# MeinMarlin.net
KiCad netlist of a schematic drawn in EasyEDA
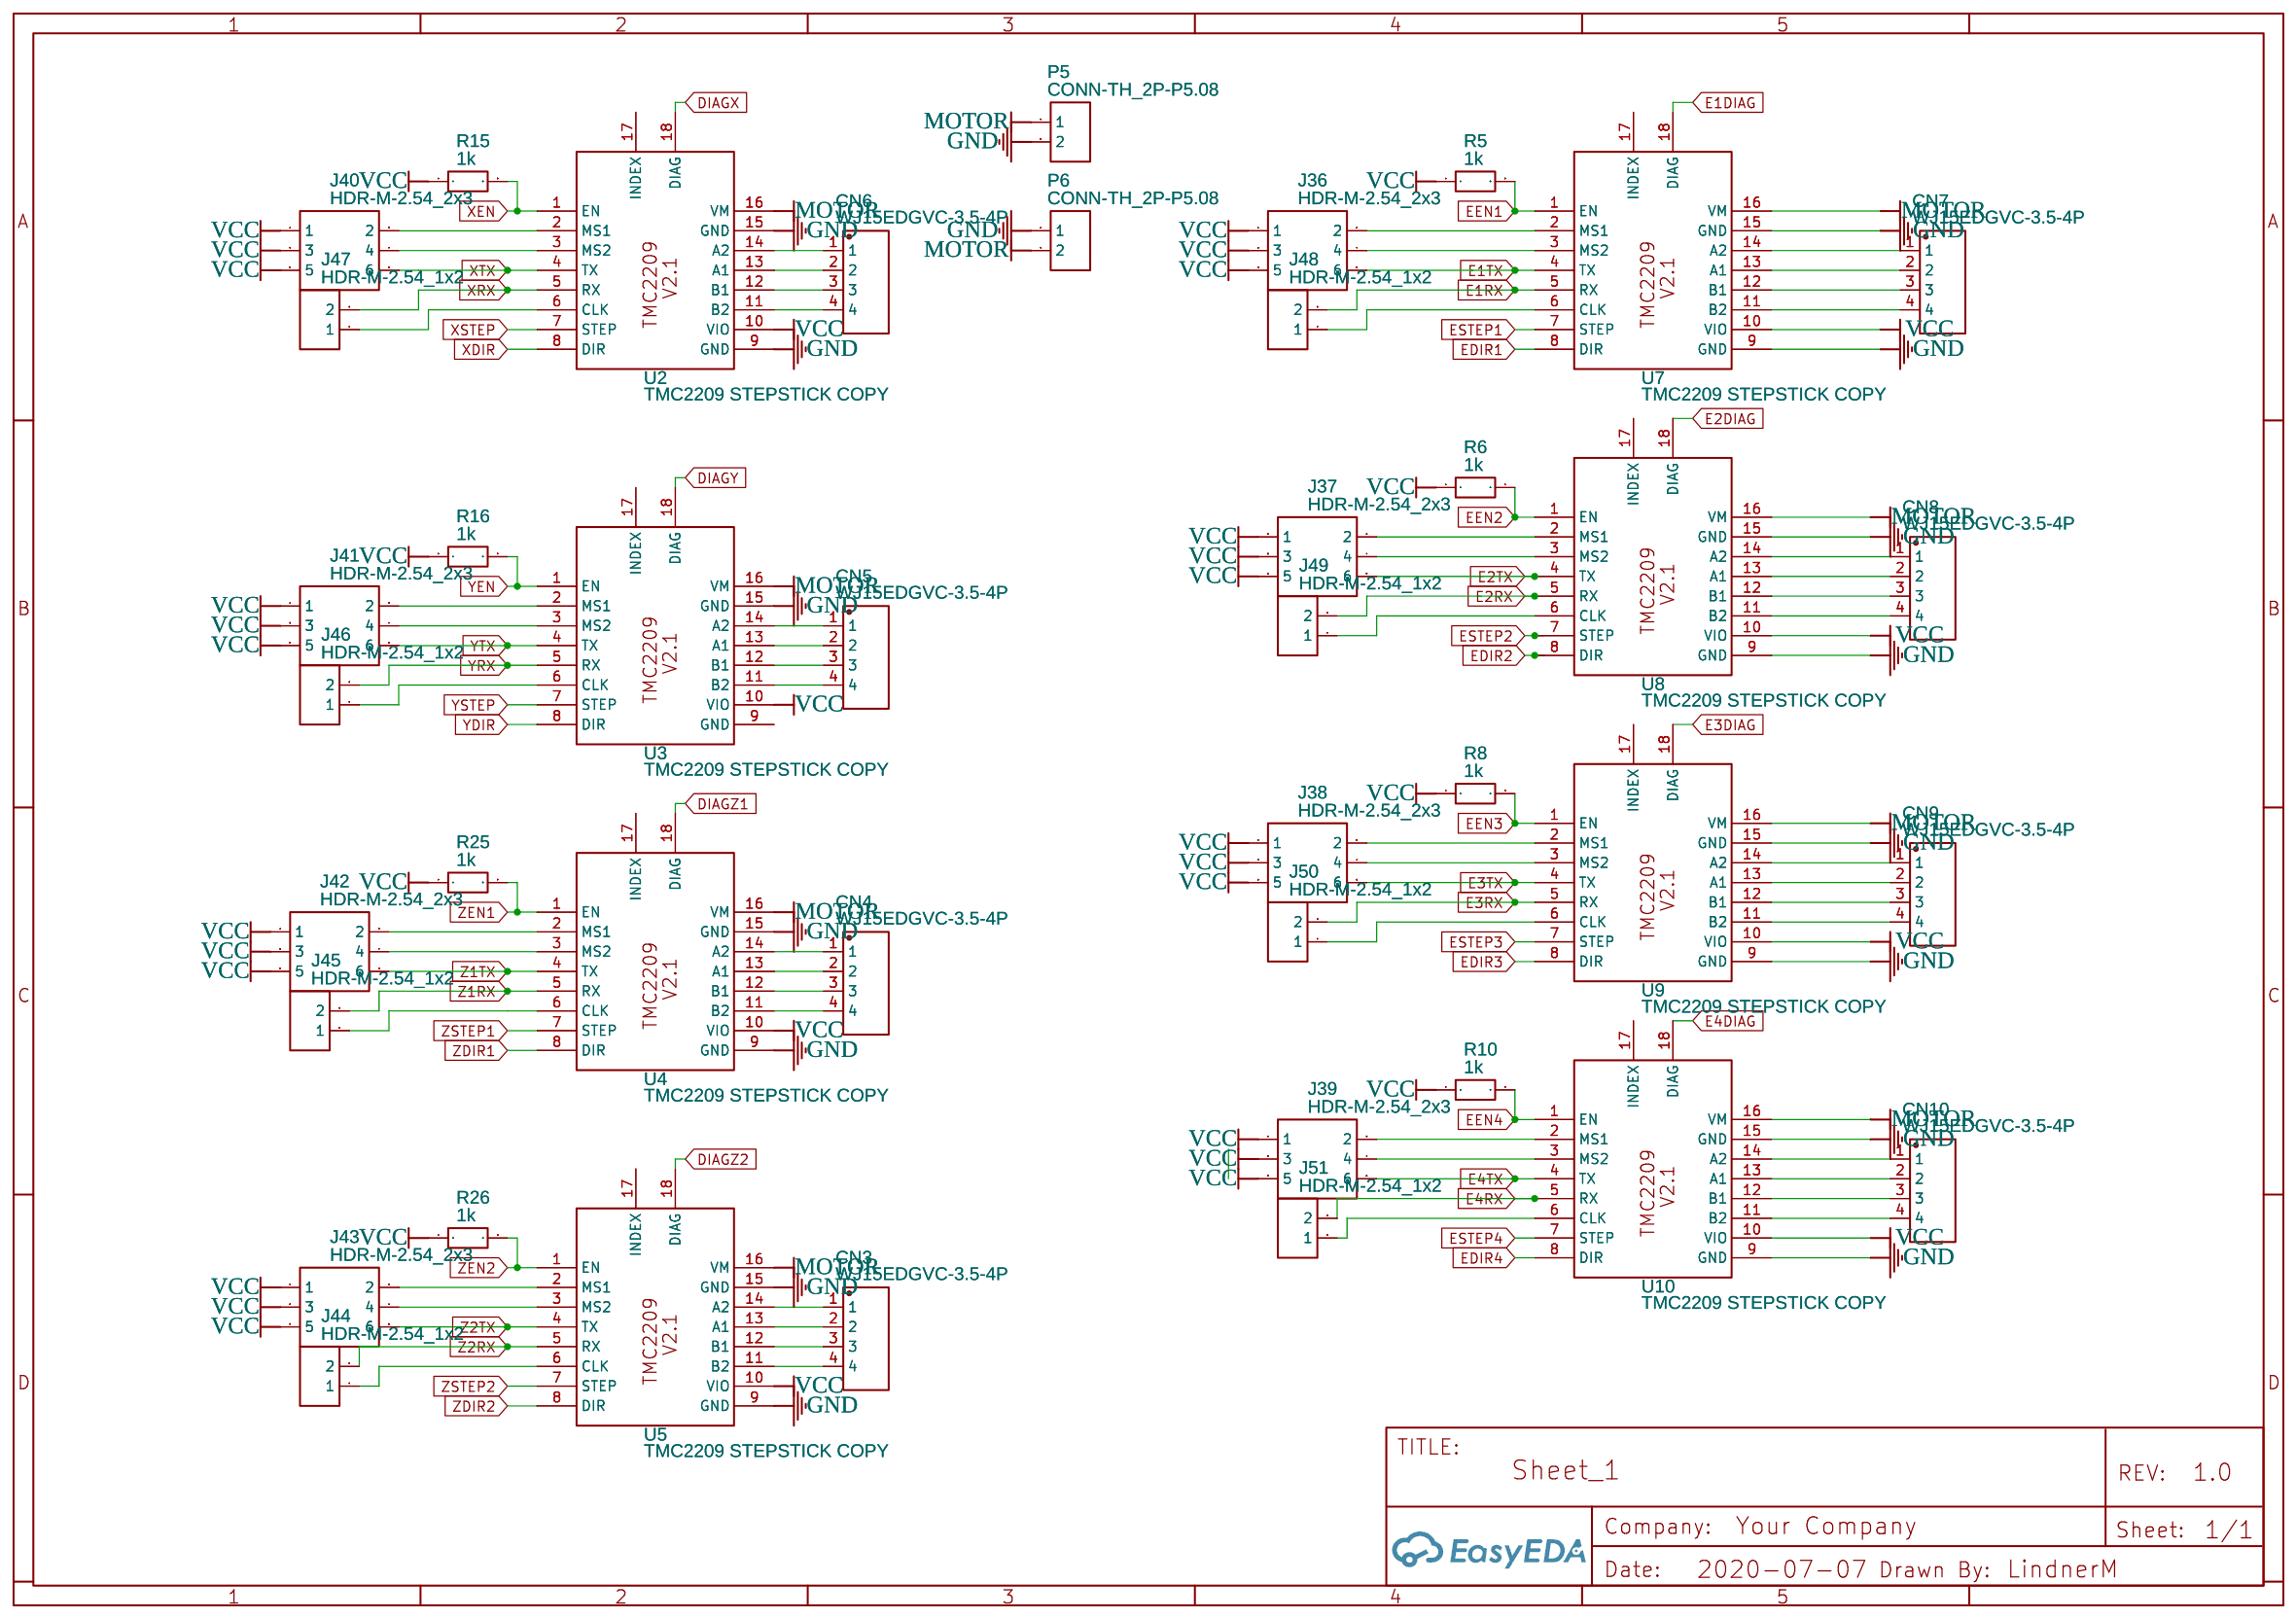
[diagram p0: STEPPER]
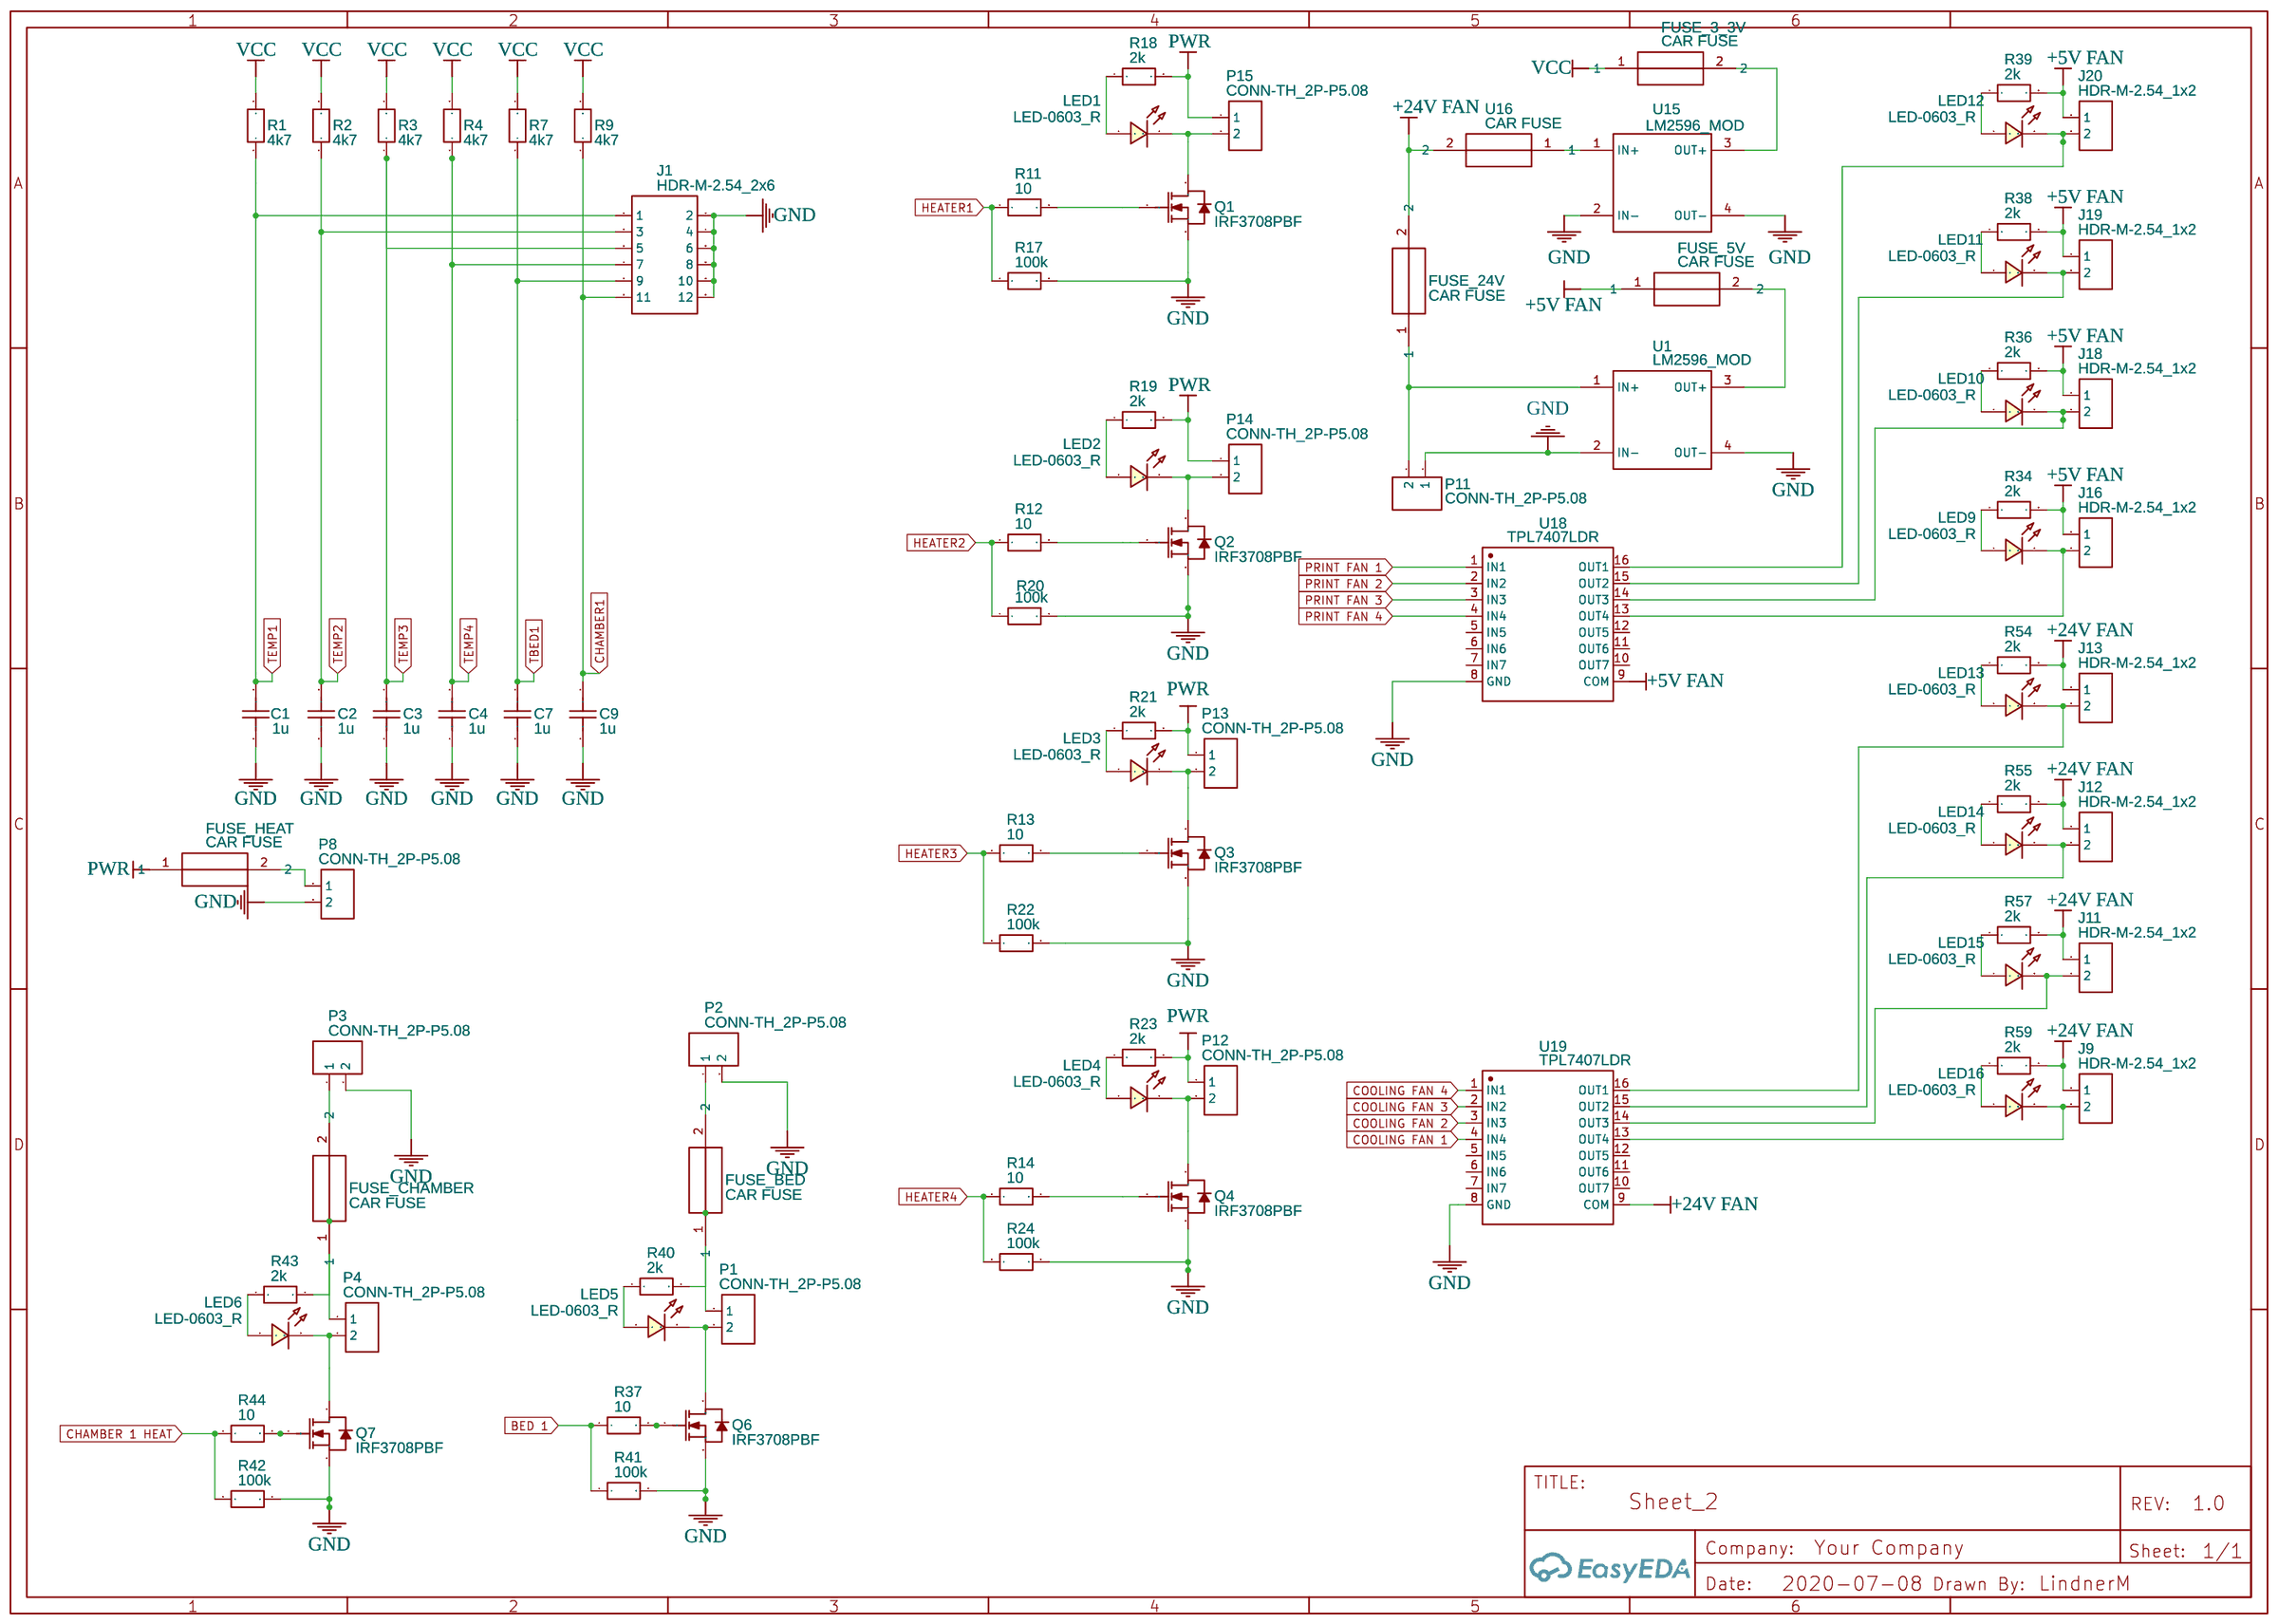
[diagram p1: FAN_HEAT_TEMP]
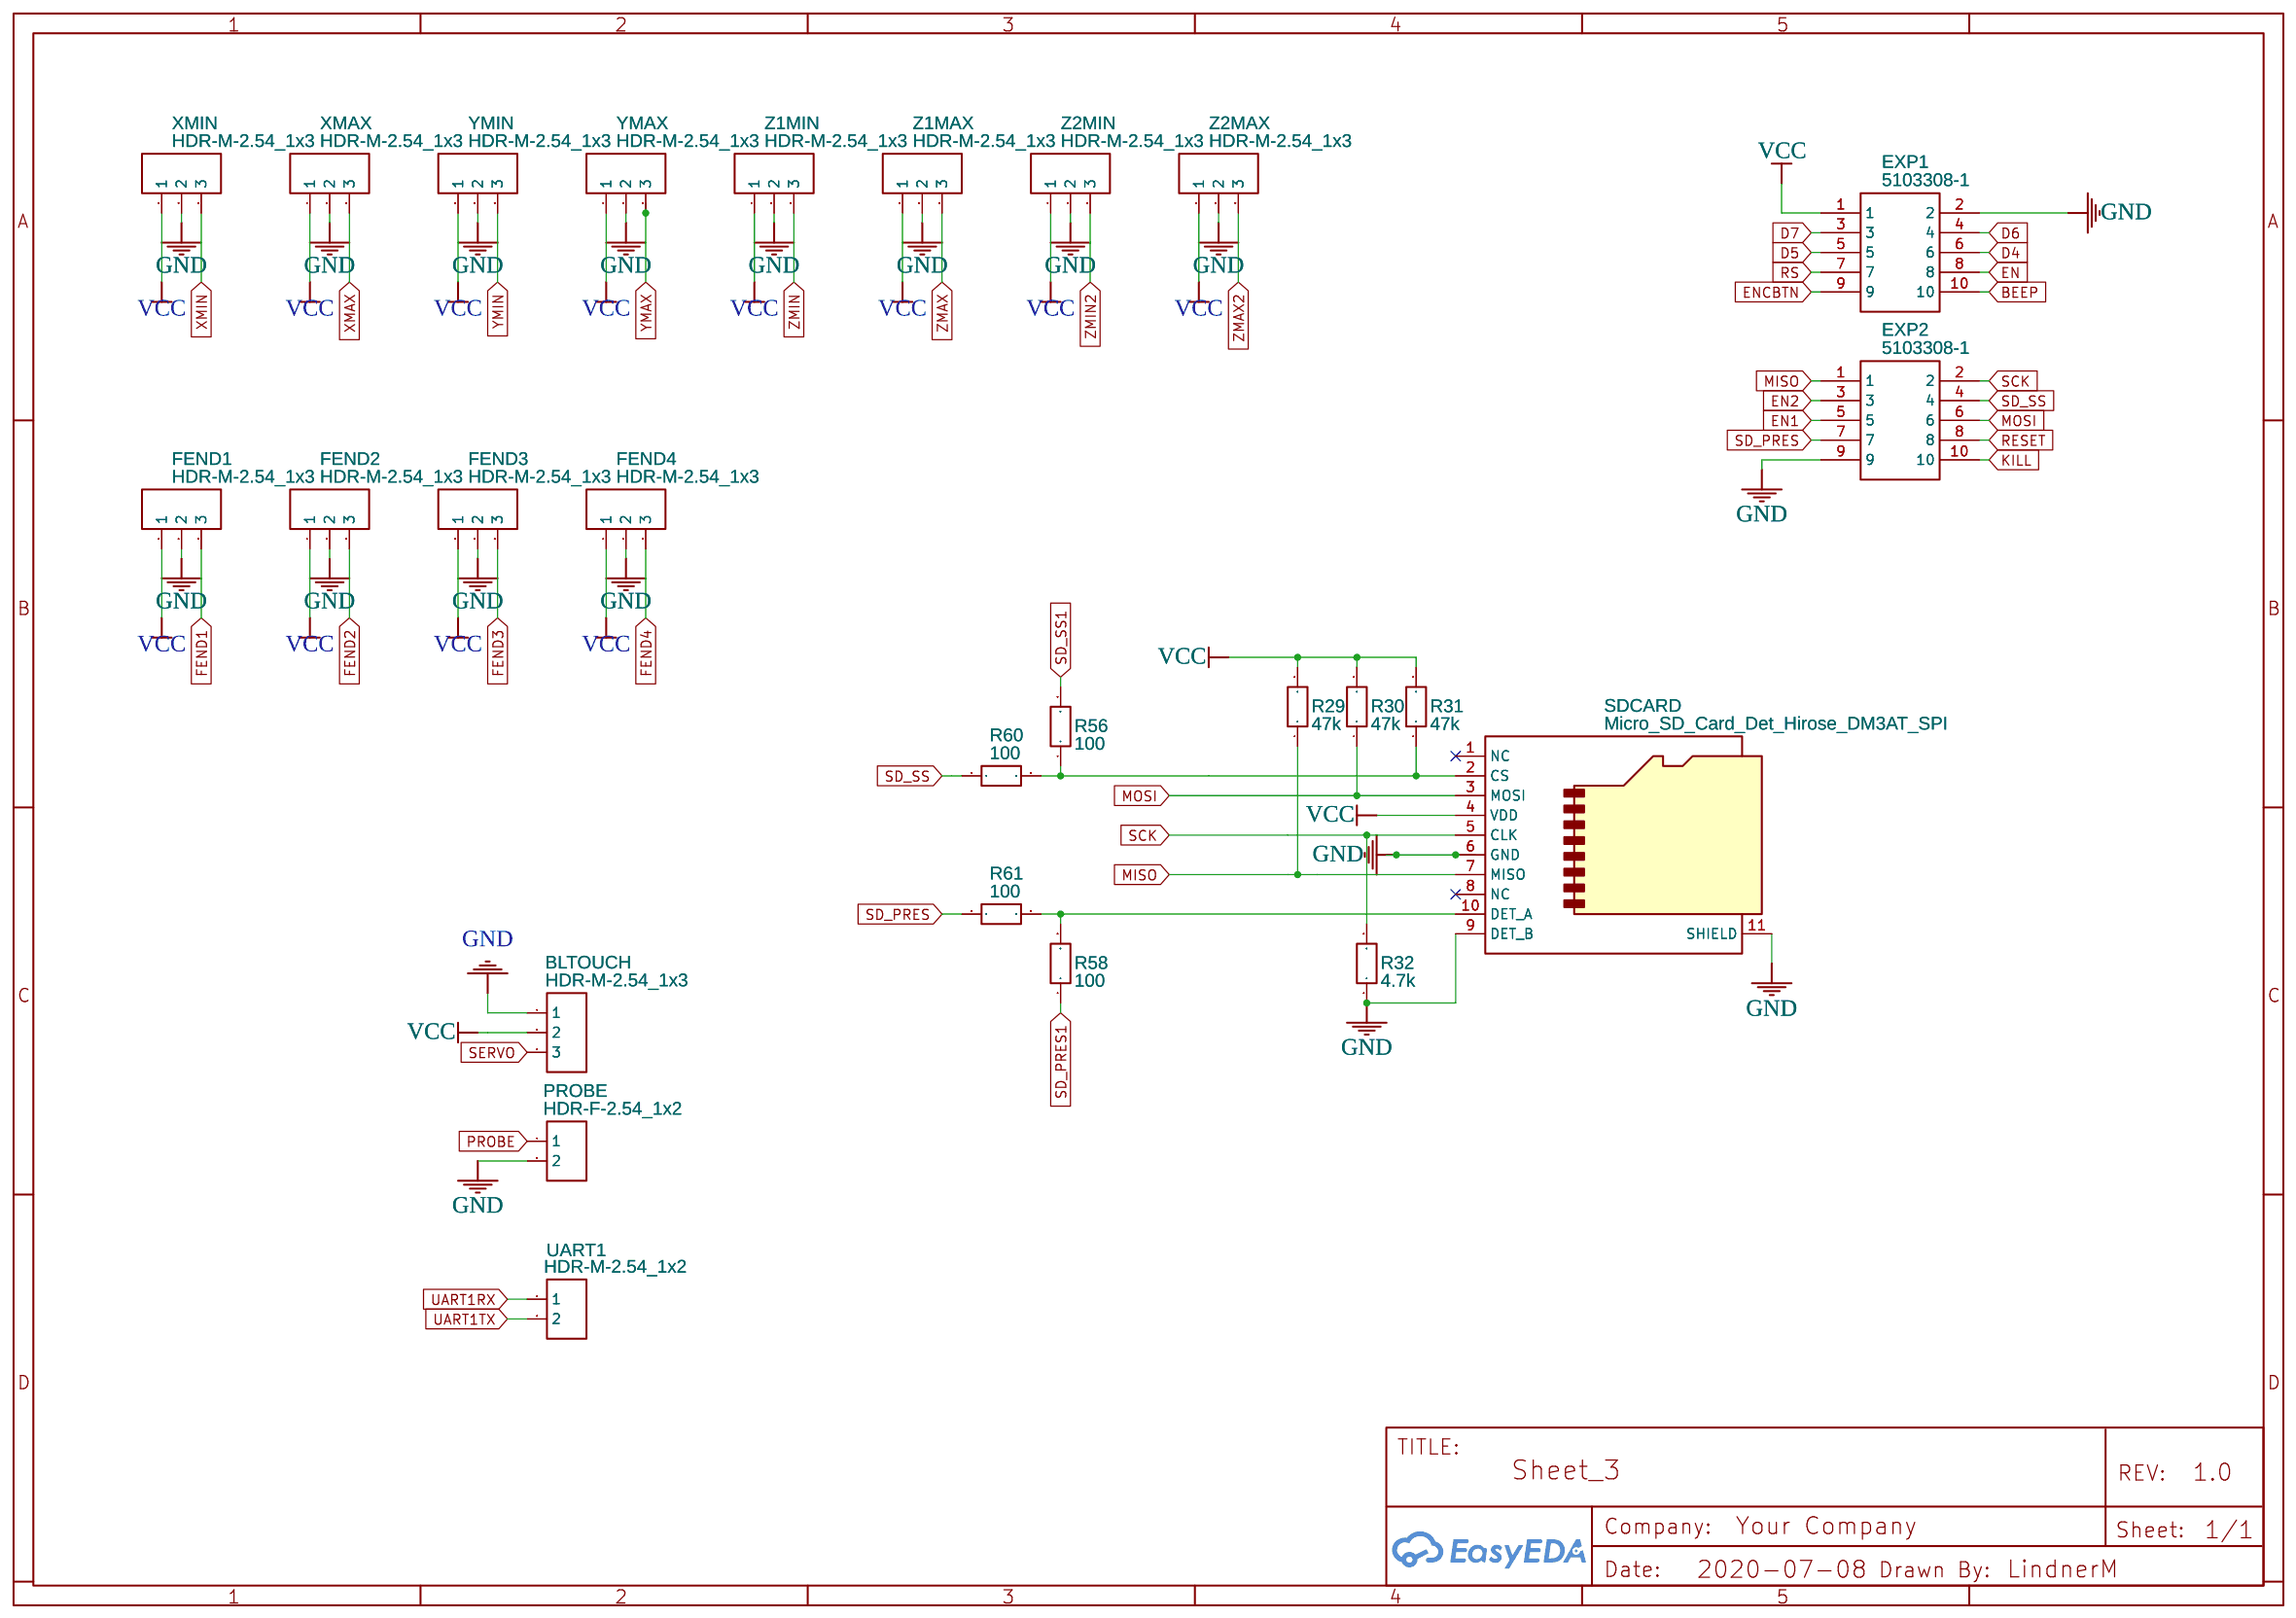
[diagram p2: SENSOR]
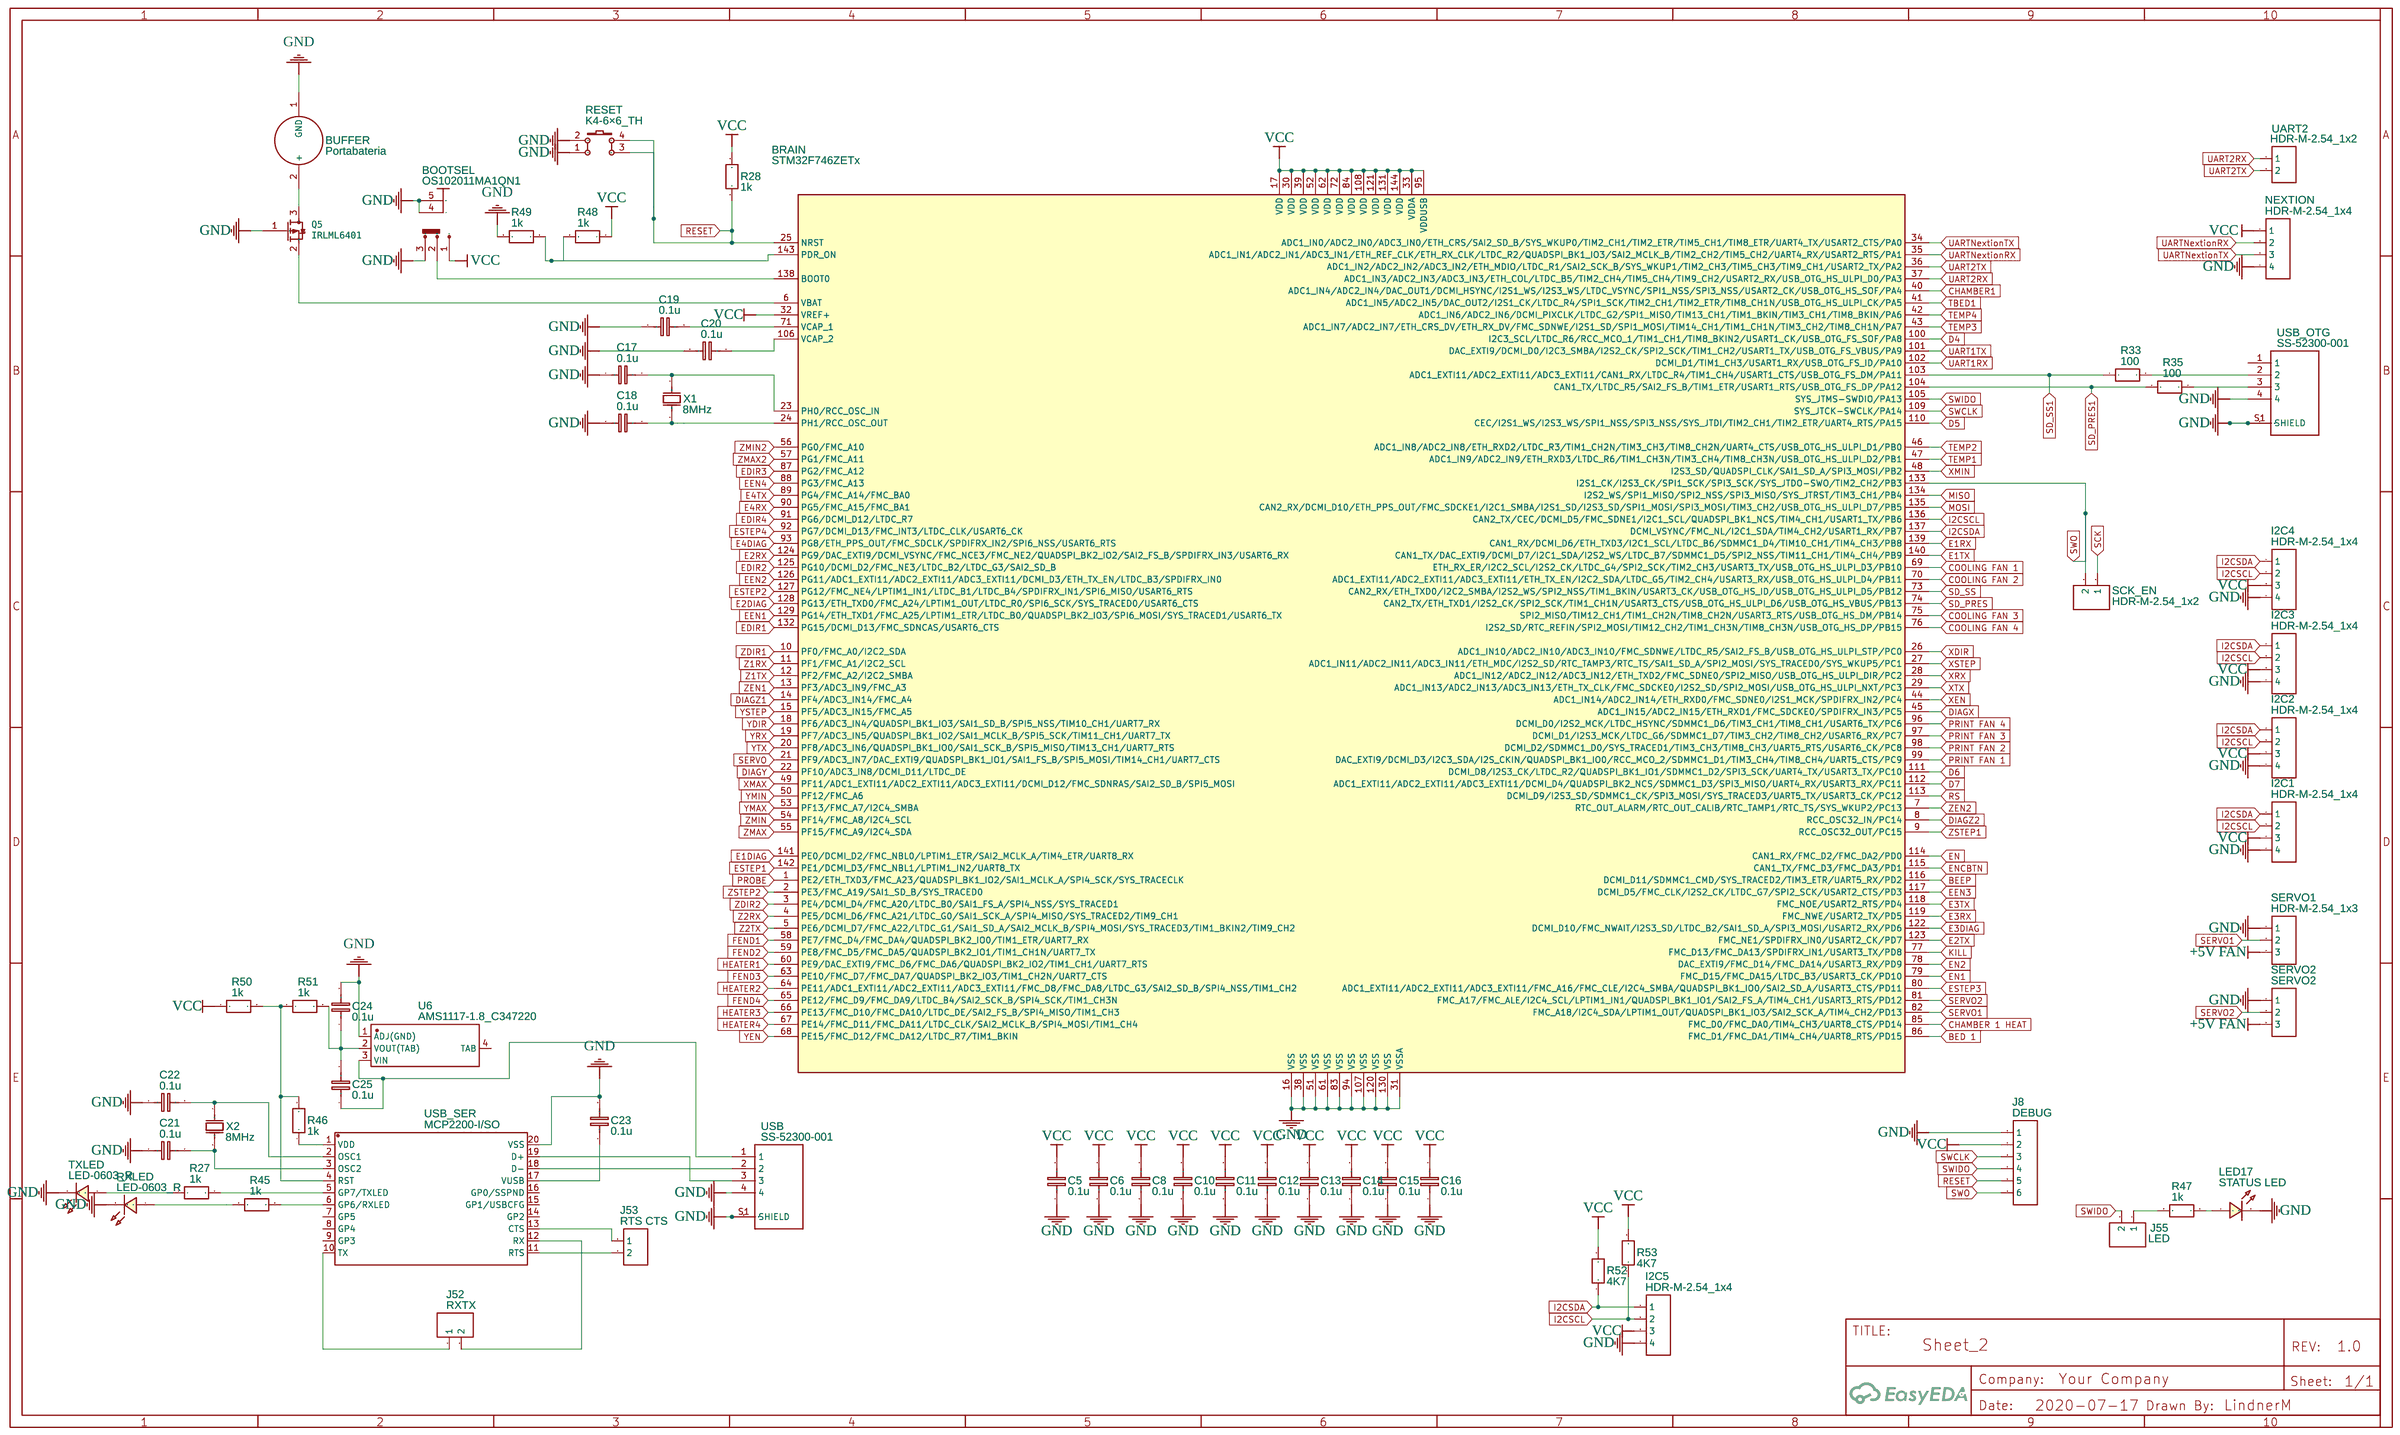
[diagram p3: MCU]

(export (version "E")
  (design (tool "Eeschema 10.0.6"))
  (components
    (comp (ref "CN3")
      (value "WJ15EDGVC-3.5-4P")
      (fields
        (field (name "BOM_Manufacturer Part") "WJ15EDGVC-3.5-4Pneedle")
        (field (name "BOM_Supplier Part") "C44917")
      )
      (libsource (lib "") (part "WJ15EDGVC-3.5-4P"))
    )
    (comp (ref "CN4")
      (value "WJ15EDGVC-3.5-4P")
      (fields
        (field (name "BOM_Manufacturer Part") "WJ15EDGVC-3.5-4Pneedle")
        (field (name "BOM_Supplier Part") "C44917")
      )
      (libsource (lib "") (part "WJ15EDGVC-3.5-4P"))
    )
    (comp (ref "CN5")
      (value "WJ15EDGVC-3.5-4P")
      (fields
        (field (name "BOM_Manufacturer Part") "WJ15EDGVC-3.5-4Pneedle")
        (field (name "BOM_Supplier Part") "C44917")
      )
      (libsource (lib "") (part "WJ15EDGVC-3.5-4P"))
    )
    (comp (ref "CN6")
      (value "WJ15EDGVC-3.5-4P")
      (fields
        (field (name "BOM_Manufacturer Part") "WJ15EDGVC-3.5-4Pneedle")
        (field (name "BOM_Supplier Part") "C44917")
      )
      (libsource (lib "") (part "WJ15EDGVC-3.5-4P"))
    )
    (comp (ref "CN7")
      (value "WJ15EDGVC-3.5-4P")
      (fields
        (field (name "BOM_Manufacturer Part") "WJ15EDGVC-3.5-4Pneedle")
        (field (name "BOM_Supplier Part") "C44917")
      )
      (libsource (lib "") (part "WJ15EDGVC-3.5-4P"))
    )
    (comp (ref "CN8")
      (value "WJ15EDGVC-3.5-4P")
      (fields
        (field (name "BOM_Manufacturer Part") "WJ15EDGVC-3.5-4Pneedle")
        (field (name "BOM_Supplier Part") "C44917")
      )
      (libsource (lib "") (part "WJ15EDGVC-3.5-4P"))
    )
    (comp (ref "CN9")
      (value "WJ15EDGVC-3.5-4P")
      (fields
        (field (name "BOM_Manufacturer Part") "WJ15EDGVC-3.5-4Pneedle")
        (field (name "BOM_Supplier Part") "C44917")
      )
      (libsource (lib "") (part "WJ15EDGVC-3.5-4P"))
    )
    (comp (ref "CN10")
      (value "WJ15EDGVC-3.5-4P")
      (fields
        (field (name "BOM_Manufacturer Part") "WJ15EDGVC-3.5-4Pneedle")
        (field (name "BOM_Supplier Part") "C44917")
      )
      (libsource (lib "") (part "WJ15EDGVC-3.5-4P"))
    )
    (comp (ref "J36")
      (value "HDR-M-2.54_2x3")
      (fields (field (name "BOM_Supplier Part") "C65114"))
      (libsource (lib "") (part "HDR-M-2.54_2x3"))
    )
    (comp (ref "J37")
      (value "HDR-M-2.54_2x3")
      (fields (field (name "BOM_Supplier Part") "C65114"))
      (libsource (lib "") (part "HDR-M-2.54_2x3"))
    )
    (comp (ref "J38")
      (value "HDR-M-2.54_2x3")
      (fields (field (name "BOM_Supplier Part") "C65114"))
      (libsource (lib "") (part "HDR-M-2.54_2x3"))
    )
    (comp (ref "J39")
      (value "HDR-M-2.54_2x3")
      (fields (field (name "BOM_Supplier Part") "C65114"))
      (libsource (lib "") (part "HDR-M-2.54_2x3"))
    )
    (comp (ref "J40")
      (value "HDR-M-2.54_2x3")
      (fields (field (name "BOM_Supplier Part") "C65114"))
      (libsource (lib "") (part "HDR-M-2.54_2x3"))
    )
    (comp (ref "J41")
      (value "HDR-M-2.54_2x3")
      (fields (field (name "BOM_Supplier Part") "C65114"))
      (libsource (lib "") (part "HDR-M-2.54_2x3"))
    )
    (comp (ref "J42")
      (value "HDR-M-2.54_2x3")
      (fields (field (name "BOM_Supplier Part") "C65114"))
      (libsource (lib "") (part "HDR-M-2.54_2x3"))
    )
    (comp (ref "J43")
      (value "HDR-M-2.54_2x3")
      (fields (field (name "BOM_Supplier Part") "C65114"))
      (libsource (lib "") (part "HDR-M-2.54_2x3"))
    )
    (comp (ref "J44")
      (value "HDR-M-2.54_1x2")
      (fields (field (name "BOM_Supplier Part") "C124375"))
      (libsource (lib "") (part "HDR-M-2.54_1x2"))
    )
    (comp (ref "J45")
      (value "HDR-M-2.54_1x2")
      (fields (field (name "BOM_Supplier Part") "C124375"))
      (libsource (lib "") (part "HDR-M-2.54_1x2"))
    )
    (comp (ref "J46")
      (value "HDR-M-2.54_1x2")
      (fields (field (name "BOM_Supplier Part") "C124375"))
      (libsource (lib "") (part "HDR-M-2.54_1x2"))
    )
    (comp (ref "J47")
      (value "HDR-M-2.54_1x2")
      (fields (field (name "BOM_Supplier Part") "C124375"))
      (libsource (lib "") (part "HDR-M-2.54_1x2"))
    )
    (comp (ref "J48")
      (value "HDR-M-2.54_1x2")
      (fields (field (name "BOM_Supplier Part") "C124375"))
      (libsource (lib "") (part "HDR-M-2.54_1x2"))
    )
    (comp (ref "J49")
      (value "HDR-M-2.54_1x2")
      (fields (field (name "BOM_Supplier Part") "C124375"))
      (libsource (lib "") (part "HDR-M-2.54_1x2"))
    )
    (comp (ref "J50")
      (value "HDR-M-2.54_1x2")
      (fields (field (name "BOM_Supplier Part") "C124375"))
      (libsource (lib "") (part "HDR-M-2.54_1x2"))
    )
    (comp (ref "J51")
      (value "HDR-M-2.54_1x2")
      (fields (field (name "BOM_Supplier Part") "C124375"))
      (libsource (lib "") (part "HDR-M-2.54_1x2"))
    )
    (comp (ref "P5") (value "CONN-TH_2P-P5.08") (libsource (lib "") (part "CONN-TH_2P-P5.08")))
    (comp (ref "P6") (value "CONN-TH_2P-P5.08") (libsource (lib "") (part "CONN-TH_2P-P5.08")))
    (comp (ref "R5") (value "1k") (libsource (lib "") (part "R_1210_EU")))
    (comp (ref "R6") (value "1k") (libsource (lib "") (part "R_1210_EU")))
    (comp (ref "R8") (value "1k") (libsource (lib "") (part "R_1210_EU")))
    (comp (ref "R10") (value "1k") (libsource (lib "") (part "R_1210_EU")))
    (comp (ref "R15") (value "1k") (libsource (lib "") (part "R_1210_EU")))
    (comp (ref "R16") (value "1k") (libsource (lib "") (part "R_1210_EU")))
    (comp (ref "R25") (value "1k") (libsource (lib "") (part "R_1210_EU")))
    (comp (ref "R26") (value "1k") (libsource (lib "") (part "R_1210_EU")))
    (comp (ref "U2") (value "TMC2209 STEPSTICK COPY") (libsource (lib "") (part "TMC2209 STEPSTICK COPY")))
    (comp (ref "U3") (value "TMC2209 STEPSTICK COPY") (libsource (lib "") (part "TMC2209 STEPSTICK COPY")))
    (comp (ref "U4") (value "TMC2209 STEPSTICK COPY") (libsource (lib "") (part "TMC2209 STEPSTICK COPY")))
    (comp (ref "U5") (value "TMC2209 STEPSTICK COPY") (libsource (lib "") (part "TMC2209 STEPSTICK COPY")))
    (comp (ref "U7") (value "TMC2209 STEPSTICK COPY") (libsource (lib "") (part "TMC2209 STEPSTICK COPY")))
    (comp (ref "U8") (value "TMC2209 STEPSTICK COPY") (libsource (lib "") (part "TMC2209 STEPSTICK COPY")))
    (comp (ref "U9") (value "TMC2209 STEPSTICK COPY") (libsource (lib "") (part "TMC2209 STEPSTICK COPY")))
    (comp (ref "U10") (value "TMC2209 STEPSTICK COPY") (libsource (lib "") (part "TMC2209 STEPSTICK COPY")))
    (comp (ref "C1") (value "1u") (libsource (lib "") (part "C_1206_US")))
    (comp (ref "C2") (value "1u") (libsource (lib "") (part "C_1206_US")))
    (comp (ref "C3") (value "1u") (libsource (lib "") (part "C_1206_US")))
    (comp (ref "C4") (value "1u") (libsource (lib "") (part "C_1206_US")))
    (comp (ref "C7") (value "1u") (libsource (lib "") (part "C_1206_US")))
    (comp (ref "C9") (value "1u") (libsource (lib "") (part "C_1206_US")))
    (comp (ref "FUSE_3_3V")
      (value "CAR FUSE")
      (fields
        (field (name "BOM_Manufacturer Part") "H1810-2X1")
        (field (name "BOM_Supplier Part") "IMAXX H1810-2X1")
      )
      (libsource (lib "") (part "CAR FUSE_1"))
    )
    (comp (ref "FUSE_5V")
      (value "CAR FUSE")
      (fields
        (field (name "BOM_Manufacturer Part") "H1810-2X1")
        (field (name "BOM_Supplier Part") "IMAXX H1810-2X1")
      )
      (libsource (lib "") (part "CAR FUSE_3"))
    )
    (comp (ref "FUSE_24V")
      (value "CAR FUSE")
      (fields
        (field (name "BOM_Manufacturer Part") "H1810-2X1")
        (field (name "BOM_Supplier Part") "IMAXX H1810-2X1")
      )
      (libsource (lib "") (part "CAR FUSE_5"))
    )
    (comp (ref "FUSE_BED")
      (value "CAR FUSE")
      (fields
        (field (name "BOM_Manufacturer Part") "H1810-2X1")
        (field (name "BOM_Supplier Part") "IMAXX H1810-2X1")
      )
      (libsource (lib "") (part "CAR FUSE_6"))
    )
    (comp (ref "FUSE_CHAMBER")
      (value "CAR FUSE")
      (fields
        (field (name "BOM_Manufacturer Part") "H1810-2X1")
        (field (name "BOM_Supplier Part") "IMAXX H1810-2X1")
      )
      (libsource (lib "") (part "CAR FUSE_4"))
    )
    (comp (ref "FUSE_HEAT")
      (value "CAR FUSE")
      (fields
        (field (name "BOM_Manufacturer Part") "H1810-2X1")
        (field (name "BOM_Supplier Part") "IMAXX H1810-2X1")
      )
      (libsource (lib "") (part "CAR FUSE"))
    )
    (comp (ref "J1")
      (value "HDR-M-2.54_2x6")
      (fields (field (name "BOM_Supplier Part") "C124388"))
      (libsource (lib "") (part "HDR-M-2.54_2x6"))
    )
    (comp (ref "J9")
      (value "HDR-M-2.54_1x2")
      (fields (field (name "BOM_Supplier Part") "C124375"))
      (libsource (lib "") (part "HDR-M-2.54_1x2"))
    )
    (comp (ref "J11")
      (value "HDR-M-2.54_1x2")
      (fields (field (name "BOM_Supplier Part") "C124375"))
      (libsource (lib "") (part "HDR-M-2.54_1x2"))
    )
    (comp (ref "J12")
      (value "HDR-M-2.54_1x2")
      (fields (field (name "BOM_Supplier Part") "C124375"))
      (libsource (lib "") (part "HDR-M-2.54_1x2"))
    )
    (comp (ref "J13")
      (value "HDR-M-2.54_1x2")
      (fields (field (name "BOM_Supplier Part") "C124375"))
      (libsource (lib "") (part "HDR-M-2.54_1x2"))
    )
    (comp (ref "J16")
      (value "HDR-M-2.54_1x2")
      (fields (field (name "BOM_Supplier Part") "C124375"))
      (libsource (lib "") (part "HDR-M-2.54_1x2"))
    )
    (comp (ref "J18")
      (value "HDR-M-2.54_1x2")
      (fields (field (name "BOM_Supplier Part") "C124375"))
      (libsource (lib "") (part "HDR-M-2.54_1x2"))
    )
    (comp (ref "J19")
      (value "HDR-M-2.54_1x2")
      (fields (field (name "BOM_Supplier Part") "C124375"))
      (libsource (lib "") (part "HDR-M-2.54_1x2"))
    )
    (comp (ref "J20")
      (value "HDR-M-2.54_1x2")
      (fields (field (name "BOM_Supplier Part") "C124375"))
      (libsource (lib "") (part "HDR-M-2.54_1x2"))
    )
    (comp (ref "LED1")
      (value "LED-0603_R")
      (fields
        (field (name "BOM_Manufacturer Part") "19-217/R6C-AL1M2VY/3T")
        (field (name "BOM_Supplier Part") "C72044")
      )
      (libsource (lib "") (part "LED-0603_R"))
    )
    (comp (ref "LED2")
      (value "LED-0603_R")
      (fields
        (field (name "BOM_Manufacturer Part") "19-217/R6C-AL1M2VY/3T")
        (field (name "BOM_Supplier Part") "C72044")
      )
      (libsource (lib "") (part "LED-0603_R"))
    )
    (comp (ref "LED3")
      (value "LED-0603_R")
      (fields
        (field (name "BOM_Manufacturer Part") "19-217/R6C-AL1M2VY/3T")
        (field (name "BOM_Supplier Part") "C72044")
      )
      (libsource (lib "") (part "LED-0603_R"))
    )
    (comp (ref "LED4")
      (value "LED-0603_R")
      (fields
        (field (name "BOM_Manufacturer Part") "19-217/R6C-AL1M2VY/3T")
        (field (name "BOM_Supplier Part") "C72044")
      )
      (libsource (lib "") (part "LED-0603_R"))
    )
    (comp (ref "LED5")
      (value "LED-0603_R")
      (fields
        (field (name "BOM_Manufacturer Part") "19-217/R6C-AL1M2VY/3T")
        (field (name "BOM_Supplier Part") "C72044")
      )
      (libsource (lib "") (part "LED-0603_R"))
    )
    (comp (ref "LED6")
      (value "LED-0603_R")
      (fields
        (field (name "BOM_Manufacturer Part") "19-217/R6C-AL1M2VY/3T")
        (field (name "BOM_Supplier Part") "C72044")
      )
      (libsource (lib "") (part "LED-0603_R"))
    )
    (comp (ref "LED9")
      (value "LED-0603_R")
      (fields
        (field (name "BOM_Manufacturer Part") "19-217/R6C-AL1M2VY/3T")
        (field (name "BOM_Supplier Part") "C72044")
      )
      (libsource (lib "") (part "LED-0603_R"))
    )
    (comp (ref "LED10")
      (value "LED-0603_R")
      (fields
        (field (name "BOM_Manufacturer Part") "19-217/R6C-AL1M2VY/3T")
        (field (name "BOM_Supplier Part") "C72044")
      )
      (libsource (lib "") (part "LED-0603_R"))
    )
    (comp (ref "LED11")
      (value "LED-0603_R")
      (fields
        (field (name "BOM_Manufacturer Part") "19-217/R6C-AL1M2VY/3T")
        (field (name "BOM_Supplier Part") "C72044")
      )
      (libsource (lib "") (part "LED-0603_R"))
    )
    (comp (ref "LED12")
      (value "LED-0603_R")
      (fields
        (field (name "BOM_Manufacturer Part") "19-217/R6C-AL1M2VY/3T")
        (field (name "BOM_Supplier Part") "C72044")
      )
      (libsource (lib "") (part "LED-0603_R"))
    )
    (comp (ref "LED13")
      (value "LED-0603_R")
      (fields
        (field (name "BOM_Manufacturer Part") "19-217/R6C-AL1M2VY/3T")
        (field (name "BOM_Supplier Part") "C72044")
      )
      (libsource (lib "") (part "LED-0603_R"))
    )
    (comp (ref "LED14")
      (value "LED-0603_R")
      (fields
        (field (name "BOM_Manufacturer Part") "19-217/R6C-AL1M2VY/3T")
        (field (name "BOM_Supplier Part") "C72044")
      )
      (libsource (lib "") (part "LED-0603_R"))
    )
    (comp (ref "LED15")
      (value "LED-0603_R")
      (fields
        (field (name "BOM_Manufacturer Part") "19-217/R6C-AL1M2VY/3T")
        (field (name "BOM_Supplier Part") "C72044")
      )
      (libsource (lib "") (part "LED-0603_R"))
    )
    (comp (ref "LED16")
      (value "LED-0603_R")
      (fields
        (field (name "BOM_Manufacturer Part") "19-217/R6C-AL1M2VY/3T")
        (field (name "BOM_Supplier Part") "C72044")
      )
      (libsource (lib "") (part "LED-0603_R"))
    )
    (comp (ref "P1") (value "CONN-TH_2P-P5.08") (libsource (lib "") (part "CONN-TH_2P-P5.08")))
    (comp (ref "P2") (value "CONN-TH_2P-P5.08") (libsource (lib "") (part "CONN-TH_2P-P5.08_1")))
    (comp (ref "P3") (value "CONN-TH_2P-P5.08") (libsource (lib "") (part "CONN-TH_2P-P5.08_1")))
    (comp (ref "P4") (value "CONN-TH_2P-P5.08") (libsource (lib "") (part "CONN-TH_2P-P5.08")))
    (comp (ref "P8") (value "CONN-TH_2P-P5.08") (libsource (lib "") (part "CONN-TH_2P-P5.08")))
    (comp (ref "P11") (value "CONN-TH_2P-P5.08") (libsource (lib "") (part "CONN-TH_2P-P5.08_2")))
    (comp (ref "P12") (value "CONN-TH_2P-P5.08") (libsource (lib "") (part "CONN-TH_2P-P5.08")))
    (comp (ref "P13") (value "CONN-TH_2P-P5.08") (libsource (lib "") (part "CONN-TH_2P-P5.08")))
    (comp (ref "P14") (value "CONN-TH_2P-P5.08") (libsource (lib "") (part "CONN-TH_2P-P5.08")))
    (comp (ref "P15") (value "CONN-TH_2P-P5.08") (libsource (lib "") (part "CONN-TH_2P-P5.08")))
    (comp (ref "Q1")
      (value "IRF3708PBF")
      (fields (field (name "BOM_Supplier Part") "C91100"))
      (libsource (lib "") (part "IRF3708PBF"))
    )
    (comp (ref "Q2")
      (value "IRF3708PBF")
      (fields (field (name "BOM_Supplier Part") "C91100"))
      (libsource (lib "") (part "IRF3708PBF"))
    )
    (comp (ref "Q3")
      (value "IRF3708PBF")
      (fields (field (name "BOM_Supplier Part") "C91100"))
      (libsource (lib "") (part "IRF3708PBF"))
    )
    (comp (ref "Q4")
      (value "IRF3708PBF")
      (fields (field (name "BOM_Supplier Part") "C91100"))
      (libsource (lib "") (part "IRF3708PBF"))
    )
    (comp (ref "Q6")
      (value "IRF3708PBF")
      (fields (field (name "BOM_Supplier Part") "C91100"))
      (libsource (lib "") (part "IRF3708PBF"))
    )
    (comp (ref "Q7")
      (value "IRF3708PBF")
      (fields (field (name "BOM_Supplier Part") "C91100"))
      (libsource (lib "") (part "IRF3708PBF"))
    )
    (comp (ref "R1") (value "4k7") (libsource (lib "") (part "R_0201_EU_1")))
    (comp (ref "R2") (value "4k7") (libsource (lib "") (part "R_0201_EU_1")))
    (comp (ref "R3") (value "4k7") (libsource (lib "") (part "R_0201_EU_1")))
    (comp (ref "R4") (value "4k7") (libsource (lib "") (part "R_0201_EU_1")))
    (comp (ref "R7") (value "4k7") (libsource (lib "") (part "R_0201_EU_1")))
    (comp (ref "R9") (value "4k7") (libsource (lib "") (part "R_0201_EU_1")))
    (comp (ref "R11") (value "10") (libsource (lib "") (part "R_0201_EU")))
    (comp (ref "R12") (value "10") (libsource (lib "") (part "R_0201_EU")))
    (comp (ref "R13") (value "10") (libsource (lib "") (part "R_0201_EU")))
    (comp (ref "R14") (value "10") (libsource (lib "") (part "R_0201_EU")))
    (comp (ref "R17") (value "100k") (libsource (lib "") (part "R_0201_EU")))
    (comp (ref "R18") (value "2k") (libsource (lib "") (part "R_0201_EU")))
    (comp (ref "R19") (value "2k") (libsource (lib "") (part "R_0201_EU")))
    (comp (ref "R20") (value "100k") (libsource (lib "") (part "R_0201_EU")))
    (comp (ref "R21") (value "2k") (libsource (lib "") (part "R_0201_EU")))
    (comp (ref "R22") (value "100k") (libsource (lib "") (part "R_0201_EU")))
    (comp (ref "R23") (value "2k") (libsource (lib "") (part "R_0201_EU")))
    (comp (ref "R24") (value "100k") (libsource (lib "") (part "R_0201_EU")))
    (comp (ref "R34") (value "2k") (libsource (lib "") (part "R_0201_EU")))
    (comp (ref "R36") (value "2k") (libsource (lib "") (part "R_0201_EU")))
    (comp (ref "R37") (value "10") (libsource (lib "") (part "R_0201_EU")))
    (comp (ref "R38") (value "2k") (libsource (lib "") (part "R_0201_EU")))
    (comp (ref "R39") (value "2k") (libsource (lib "") (part "R_0201_EU")))
    (comp (ref "R40") (value "2k") (libsource (lib "") (part "R_0201_EU")))
    (comp (ref "R41") (value "100k") (libsource (lib "") (part "R_0201_EU")))
    (comp (ref "R42") (value "100k") (libsource (lib "") (part "R_0201_EU")))
    (comp (ref "R43") (value "2k") (libsource (lib "") (part "R_0201_EU")))
    (comp (ref "R44") (value "10") (libsource (lib "") (part "R_0201_EU")))
    (comp (ref "R54") (value "2k") (libsource (lib "") (part "R_0201_EU")))
    (comp (ref "R55") (value "2k") (libsource (lib "") (part "R_0201_EU")))
    (comp (ref "R57") (value "2k") (libsource (lib "") (part "R_0201_EU")))
    (comp (ref "R59") (value "2k") (libsource (lib "") (part "R_0201_EU")))
    (comp (ref "U1")
      (value "LM2596_MOD")
      (fields (field (name "BOM_Manufacturer Part") "LM2596S"))
      (libsource (lib "") (part "LM2596_MOD"))
    )
    (comp (ref "U15")
      (value "LM2596_MOD")
      (fields (field (name "BOM_Manufacturer Part") "LM2596S"))
      (libsource (lib "") (part "LM2596_MOD"))
    )
    (comp (ref "U16")
      (value "CAR FUSE")
      (fields
        (field (name "BOM_Manufacturer Part") "H1810-2X1")
        (field (name "BOM_Supplier Part") "IMAXX H1810-2X1")
      )
      (libsource (lib "") (part "CAR FUSE_2"))
    )
    (comp (ref "U18")
      (value "TPL7407LDR")
      (fields (field (name "BOM_Supplier Part") "C139663"))
      (libsource (lib "") (part "TPL7407LDR"))
    )
    (comp (ref "U19")
      (value "TPL7407LDR")
      (fields (field (name "BOM_Supplier Part") "C139663"))
      (libsource (lib "") (part "TPL7407LDR"))
    )
    (comp (ref "BLTOUCH")
      (value "HDR-M-2.54_1x3")
      (fields (field (name "BOM_Supplier Part") "C180248"))
      (libsource (lib "") (part "HDR-M-2.54_1x3_1"))
    )
    (comp (ref "EXP1")
      (value "5103308-1")
      (fields (field (name "BOM_Supplier Part") "C86466"))
      (libsource (lib "") (part "5103308-1"))
    )
    (comp (ref "EXP2")
      (value "5103308-1")
      (fields (field (name "BOM_Supplier Part") "C86466"))
      (libsource (lib "") (part "5103308-1"))
    )
    (comp (ref "FEND1")
      (value "HDR-M-2.54_1x3")
      (fields (field (name "BOM_Supplier Part") "C180248"))
      (libsource (lib "") (part "HDR-M-2.54_1x3_4"))
    )
    (comp (ref "FEND2")
      (value "HDR-M-2.54_1x3")
      (fields (field (name "BOM_Supplier Part") "C180248"))
      (libsource (lib "") (part "HDR-M-2.54_1x3_4"))
    )
    (comp (ref "FEND3")
      (value "HDR-M-2.54_1x3")
      (fields (field (name "BOM_Supplier Part") "C180248"))
      (libsource (lib "") (part "HDR-M-2.54_1x3_4"))
    )
    (comp (ref "FEND4")
      (value "HDR-M-2.54_1x3")
      (fields (field (name "BOM_Supplier Part") "C180248"))
      (libsource (lib "") (part "HDR-M-2.54_1x3_4"))
    )
    (comp (ref "PROBE")
      (value "HDR-F-2.54_1x2")
      (fields (field (name "BOM_Supplier Part") "C49661"))
      (libsource (lib "") (part "HDR-F-2.54_1x2"))
    )
    (comp (ref "R29") (value "47k") (libsource (lib "") (part "R_1206_EU")))
    (comp (ref "R30") (value "47k") (libsource (lib "") (part "R_1206_EU")))
    (comp (ref "R31") (value "47k") (libsource (lib "") (part "R_1206_EU")))
    (comp (ref "R32") (value "4.7k") (libsource (lib "") (part "R_1206_EU")))
    (comp (ref "R56") (value "100") (libsource (lib "") (part "R_1206_EU")))
    (comp (ref "R58") (value "100") (libsource (lib "") (part "R_1206_EU")))
    (comp (ref "R60") (value "100") (libsource (lib "") (part "R_1206_EU_1")))
    (comp (ref "R61") (value "100") (libsource (lib "") (part "R_1206_EU_1")))
    (comp (ref "SDCARD")
      (value "Micro_SD_Card_Det_Hirose_DM3AT_SPI")
      (libsource (lib "") (part "Micro_SD_Card_Det_Hirose_DM3AT_SPI"))
    )
    (comp (ref "UART1")
      (value "HDR-M-2.54_1x2")
      (fields (field (name "BOM_Supplier Part") "C124375"))
      (libsource (lib "") (part "HDR-M-2.54_1x2"))
    )
    (comp (ref "XMAX")
      (value "HDR-M-2.54_1x3")
      (fields (field (name "BOM_Supplier Part") "C180248"))
      (libsource (lib "") (part "HDR-M-2.54_1x3_5"))
    )
    (comp (ref "XMIN")
      (value "HDR-M-2.54_1x3")
      (fields (field (name "BOM_Supplier Part") "C180248"))
      (libsource (lib "") (part "HDR-M-2.54_1x3_3"))
    )
    (comp (ref "YMAX")
      (value "HDR-M-2.54_1x3")
      (fields (field (name "BOM_Supplier Part") "C180248"))
      (libsource (lib "") (part "HDR-M-2.54_1x3_9"))
    )
    (comp (ref "YMIN")
      (value "HDR-M-2.54_1x3")
      (fields (field (name "BOM_Supplier Part") "C180248"))
      (libsource (lib "") (part "HDR-M-2.54_1x3_6"))
    )
    (comp (ref "Z1MAX")
      (value "HDR-M-2.54_1x3")
      (fields (field (name "BOM_Supplier Part") "C180248"))
      (libsource (lib "") (part "HDR-M-2.54_1x3_2"))
    )
    (comp (ref "Z1MIN")
      (value "HDR-M-2.54_1x3")
      (fields (field (name "BOM_Supplier Part") "C180248"))
      (libsource (lib "") (part "HDR-M-2.54_1x3_7"))
    )
    (comp (ref "Z2MAX")
      (value "HDR-M-2.54_1x3")
      (fields (field (name "BOM_Supplier Part") "C180248"))
      (libsource (lib "") (part "HDR-M-2.54_1x3_8"))
    )
    (comp (ref "Z2MIN")
      (value "HDR-M-2.54_1x3")
      (fields (field (name "BOM_Supplier Part") "C180248"))
      (libsource (lib "") (part "HDR-M-2.54_1x3"))
    )
    (comp (ref "BOOTSEL")
      (value "OS102011MA1QN1")
      (fields (field (name "BOM_Supplier Part") "C226259"))
      (libsource (lib "") (part "OS102011MA1QN1"))
    )
    (comp (ref "BRAIN") (value "STM32F746ZETx") (libsource (lib "") (part "STM32F746ZETx")))
    (comp (ref "BUFFER")
      (value "Portabateria")
      (fields (field (name "BOM_Manufacturer Part") "VBH2032-1"))
      (libsource (lib "") (part "Portabateria"))
    )
    (comp (ref "C5") (value "0.1u") (libsource (lib "") (part "C_1206_EU_3")))
    (comp (ref "C6") (value "0.1u") (libsource (lib "") (part "C_1206_EU_3")))
    (comp (ref "C8") (value "0.1u") (libsource (lib "") (part "C_1206_EU")))
    (comp (ref "C10") (value "0.1u") (libsource (lib "") (part "C_1206_EU")))
    (comp (ref "C11") (value "0.1u") (libsource (lib "") (part "C_1206_EU")))
    (comp (ref "C12") (value "0.1u") (libsource (lib "") (part "C_1206_EU")))
    (comp (ref "C13") (value "0.1u") (libsource (lib "") (part "C_1206_EU")))
    (comp (ref "C14") (value "0.1u") (libsource (lib "") (part "C_1206_EU")))
    (comp (ref "C15") (value "0.1u") (libsource (lib "") (part "C_1206_EU")))
    (comp (ref "C16") (value "0.1u") (libsource (lib "") (part "C_1206_EU")))
    (comp (ref "C17") (value "0.1u") (libsource (lib "") (part "C_1206_EU_2")))
    (comp (ref "C18") (value "0.1u") (libsource (lib "") (part "C_1206_EU_2")))
    (comp (ref "C19") (value "0.1u") (libsource (lib "") (part "C_1206_EU_1")))
    (comp (ref "C20") (value "0.1u") (libsource (lib "") (part "C_1206_EU_1")))
    (comp (ref "C21") (value "0.1u") (libsource (lib "") (part "C_1206_EU_1")))
    (comp (ref "C22") (value "0.1u") (libsource (lib "") (part "C_1206_EU_1")))
    (comp (ref "C23") (value "0.1u") (libsource (lib "") (part "C_1206_EU")))
    (comp (ref "C24") (value "0.1u") (libsource (lib "") (part "C_1206_EU")))
    (comp (ref "C25") (value "0.1u") (libsource (lib "") (part "C_1206_EU_4")))
    (comp (ref "I2C1")
      (value "HDR-M-2.54_1x4")
      (fields (field (name "BOM_Supplier Part") "C124378"))
      (libsource (lib "") (part "HDR-M-2.54_1x4_1"))
    )
    (comp (ref "I2C2")
      (value "HDR-M-2.54_1x4")
      (fields (field (name "BOM_Supplier Part") "C124378"))
      (libsource (lib "") (part "HDR-M-2.54_1x4_1"))
    )
    (comp (ref "I2C3")
      (value "HDR-M-2.54_1x4")
      (fields (field (name "BOM_Supplier Part") "C124378"))
      (libsource (lib "") (part "HDR-M-2.54_1x4_1"))
    )
    (comp (ref "I2C4")
      (value "HDR-M-2.54_1x4")
      (fields (field (name "BOM_Supplier Part") "C124378"))
      (libsource (lib "") (part "HDR-M-2.54_1x4_1"))
    )
    (comp (ref "I2C5")
      (value "HDR-M-2.54_1x4")
      (fields (field (name "BOM_Supplier Part") "C124378"))
      (libsource (lib "") (part "HDR-M-2.54_1x4_1"))
    )
    (comp (ref "J8")
      (value "DEBUG")
      (fields (field (name "BOM_Supplier Part") "C190819"))
      (libsource (lib "") (part "HDR-M-2.54_1x6"))
    )
    (comp (ref "J52")
      (value "RXTX")
      (fields (field (name "BOM_Supplier Part") "C124375"))
      (libsource (lib "") (part "HDR-M-2.54_1x2_3"))
    )
    (comp (ref "J53")
      (value "RTS CTS")
      (fields (field (name "BOM_Supplier Part") "C124375"))
      (libsource (lib "") (part "HDR-M-2.54_1x2_4"))
    )
    (comp (ref "J55")
      (value "LED")
      (fields (field (name "BOM_Supplier Part") "C124375"))
      (libsource (lib "") (part "HDR-M-2.54_1x2_2"))
    )
    (comp (ref "LED17")
      (value "STATUS LED")
      (fields
        (field (name "BOM_Manufacturer Part") "19-217/R6C-AL1M2VY/3T")
        (field (name "BOM_Supplier Part") "C72044")
      )
      (libsource (lib "") (part "LED-0603_R"))
    )
    (comp (ref "NEXTION")
      (value "HDR-M-2.54_1x4")
      (fields (field (name "BOM_Supplier Part") "C124378"))
      (libsource (lib "") (part "HDR-M-2.54_1x4"))
    )
    (comp (ref "Q5") (value "IRLML6401") (libsource (lib "") (part "Unknown_-180_-690")))
    (comp (ref "R27") (value "1k") (libsource (lib "") (part "R_1206_EU")))
    (comp (ref "R28") (value "1k") (libsource (lib "") (part "R_1206_EU_1")))
    (comp (ref "R33") (value "100") (libsource (lib "") (part "R_1206_EU")))
    (comp (ref "R35") (value "100") (libsource (lib "") (part "R_1206_EU")))
    (comp (ref "R45") (value "1k") (libsource (lib "") (part "R_1206_EU")))
    (comp (ref "R46") (value "1k") (libsource (lib "") (part "R_1206_EU_1")))
    (comp (ref "R47") (value "1k") (libsource (lib "") (part "R_1206_EU_2")))
    (comp (ref "R48") (value "1k") (libsource (lib "") (part "R_1206_EU_2")))
    (comp (ref "R49") (value "1k") (libsource (lib "") (part "R_1206_EU_2")))
    (comp (ref "R50") (value "1k") (libsource (lib "") (part "R_1206_EU")))
    (comp (ref "R51") (value "1k") (libsource (lib "") (part "R_1206_EU")))
    (comp (ref "R52") (value "4K7") (libsource (lib "") (part "R_1206_EU_1")))
    (comp (ref "R53") (value "4K7") (libsource (lib "") (part "R_1206_EU_1")))
    (comp (ref "RESET")
      (value "K4-6×6_TH")
      (fields
        (field (name "BOM_Manufacturer Part") "K2-1102DP-E4SW-04")
        (field (name "BOM_Supplier Part") "C136684")
      )
      (libsource (lib "") (part "K4-6×6_TH"))
    )
    (comp (ref "RXLED")
      (value "LED-0603_R")
      (fields
        (field (name "BOM_Manufacturer Part") "19-217/R6C-AL1M2VY/3T")
        (field (name "BOM_Supplier Part") "C72044")
      )
      (libsource (lib "") (part "LED-0603_R_2"))
    )
    (comp (ref "SCK_EN")
      (value "HDR-M-2.54_1x2")
      (fields (field (name "BOM_Supplier Part") "C124375"))
      (libsource (lib "") (part "HDR-M-2.54_1x2_1"))
    )
    (comp (ref "SERVO1")
      (value "HDR-M-2.54_1x3")
      (fields (field (name "BOM_Supplier Part") "C180248"))
      (libsource (lib "") (part "HDR-M-2.54_1x3"))
    )
    (comp (ref "SERVO2")
      (value "SERVO2")
      (fields (field (name "BOM_Supplier Part") "C180248"))
      (libsource (lib "") (part "HDR-M-2.54_1x3"))
    )
    (comp (ref "TXLED")
      (value "LED-0603_R")
      (fields
        (field (name "BOM_Manufacturer Part") "19-217/R6C-AL1M2VY/3T")
        (field (name "BOM_Supplier Part") "C72044")
      )
      (libsource (lib "") (part "LED-0603_R_1"))
    )
    (comp (ref "U6")
      (value "AMS1117-1.8_C347220")
      (fields
        (field (name "BOM_Manufacturer Part") "AMS1117-1.8")
        (field (name "BOM_Supplier Part") "C347220")
      )
      (libsource (lib "") (part "AMS1117-1.8_C347220"))
    )
    (comp (ref "UART2")
      (value "HDR-M-2.54_1x2")
      (fields (field (name "BOM_Supplier Part") "C124375"))
      (libsource (lib "") (part "HDR-M-2.54_1x2"))
    )
    (comp (ref "USB") (value "SS-52300-001") (libsource (lib "") (part "SS-52300-001")))
    (comp (ref "USB_OTG") (value "SS-52300-001") (libsource (lib "") (part "SS-52300-001_1")))
    (comp (ref "USB_SER")
      (value "MCP2200-I/SO")
      (fields (field (name "BOM_Supplier Part") "C220734"))
      (libsource (lib "") (part "MCP2200-I/SO"))
    )
    (comp (ref "X1")
      (value "8MHz")
      (fields
        (field (name "BOM_Manufacturer Part") "HC-49SM8MHz20pF30ppm")
        (field (name "BOM_Supplier Part") "C107426")
      )
      (libsource (lib "") (part "HC-49SM8MHz20pF30ppm"))
    )
    (comp (ref "X2")
      (value "8MHz")
      (fields
        (field (name "BOM_Manufacturer Part") "HC-49SM8MHz20pF30ppm")
        (field (name "BOM_Supplier Part") "C107426")
      )
      (libsource (lib "") (part "HC-49SM8MHz20pF30ppm"))
    )
  )
  (nets
    (net (code "1") (name "+5V FAN") (class "Default")
      (node (ref "FUSE_5V") (pin "1") (pinfunction "1_1") (pintype "unspecified"))
      (node (ref "J16") (pin "1") (pinfunction "1_1") (pintype "unspecified"))
      (node (ref "J18") (pin "1") (pinfunction "1_1") (pintype "unspecified"))
      (node (ref "J19") (pin "1") (pinfunction "1_1") (pintype "unspecified"))
      (node (ref "J20") (pin "1") (pinfunction "1_1") (pintype "unspecified"))
      (node (ref "R34") (pin "2") (pinfunction "2_2") (pintype "unspecified"))
      (node (ref "R36") (pin "2") (pinfunction "2_2") (pintype "unspecified"))
      (node (ref "R38") (pin "2") (pinfunction "2_2") (pintype "unspecified"))
      (node (ref "R39") (pin "2") (pinfunction "2_2") (pintype "unspecified"))
      (node (ref "SERVO1") (pin "3") (pinfunction "3_3") (pintype "input"))
      (node (ref "SERVO2") (pin "3") (pinfunction "3_3") (pintype "input"))
      (node (ref "U18") (pin "9") (pinfunction "COM_9") (pintype "unspecified"))
    )
    (net (code "2") (name "+24V FAN") (class "Default")
      (node (ref "FUSE_24V") (pin "2") (pinfunction "2_2") (pintype "unspecified"))
      (node (ref "J11") (pin "1") (pinfunction "1_1") (pintype "unspecified"))
      (node (ref "J12") (pin "1") (pinfunction "1_1") (pintype "unspecified"))
      (node (ref "J13") (pin "1") (pinfunction "1_1") (pintype "unspecified"))
      (node (ref "J9") (pin "1") (pinfunction "1_1") (pintype "unspecified"))
      (node (ref "R54") (pin "2") (pinfunction "2_2") (pintype "unspecified"))
      (node (ref "R55") (pin "2") (pinfunction "2_2") (pintype "unspecified"))
      (node (ref "R57") (pin "2") (pinfunction "2_2") (pintype "unspecified"))
      (node (ref "R59") (pin "2") (pinfunction "2_2") (pintype "unspecified"))
      (node (ref "U16") (pin "2") (pinfunction "2_2") (pintype "unspecified"))
      (node (ref "U19") (pin "9") (pinfunction "COM_9") (pintype "unspecified"))
    )
    (net (code "3") (name "BED 1") (class "Default")
      (node (ref "BRAIN") (pin "86") (pinfunction "FMC_D1/FMC_DA1/TIM4_CH4/UART8_RTS/PD15_86") (pintype "bidirectional"))
      (node (ref "R37") (pin "1") (pinfunction "1_1") (pintype "unspecified"))
      (node (ref "R41") (pin "1") (pinfunction "1_1") (pintype "unspecified"))
    )
    (net (code "4") (name "BEEP") (class "Default")
      (node (ref "BRAIN") (pin "116") (pinfunction "DCMI_D11/SDMMC1_CMD/SYS_TRACED2/TIM3_ETR/UART5_RX/PD2_116") (pintype "bidirectional"))
      (node (ref "EXP1") (pin "10") (pinfunction "10_10") (pintype "unspecified"))
    )
    (net (code "5") (name "CHAMBER 1 HEAT") (class "Default")
      (node (ref "BRAIN") (pin "85") (pinfunction "FMC_D0/FMC_DA0/TIM4_CH3/UART8_CTS/PD14_85") (pintype "bidirectional"))
      (node (ref "R42") (pin "1") (pinfunction "1_1") (pintype "unspecified"))
      (node (ref "R44") (pin "1") (pinfunction "1_1") (pintype "unspecified"))
    )
    (net (code "6") (name "CHAMBER1") (class "Default")
      (node (ref "BRAIN") (pin "40") (pinfunction "ADC1_IN4/ADC2_IN4/DAC_OUT1/DCMI_HSYNC/I2S1_WS/I2S3_WS/LTDC_VSYNC/SPI1_NSS/SPI3_NSS/USART2_CK/USB_OTG_HS_SOF/PA4_40") (pintype "bidirectional"))
      (node (ref "C9") (pin "2") (pinfunction "2_2") (pintype "unspecified"))
      (node (ref "J1") (pin "11") (pinfunction "11_11") (pintype "unspecified"))
      (node (ref "R9") (pin "1") (pinfunction "1_1") (pintype "unspecified"))
    )
    (net (code "7") (name "COOLING FAN 1") (class "Default")
      (node (ref "BRAIN") (pin "69") (pinfunction "ETH_RX_ER/I2C2_SCL/I2S2_CK/LTDC_G4/SPI2_SCK/TIM2_CH3/USART3_TX/USB_OTG_HS_ULPI_D3/PB10_69") (pintype "bidirectional"))
      (node (ref "U19") (pin "4") (pinfunction "IN4_4") (pintype "unspecified"))
    )
    (net (code "8") (name "COOLING FAN 2") (class "Default")
      (node (ref "BRAIN") (pin "70") (pinfunction "ADC1_EXTI11/ADC2_EXTI11/ADC3_EXTI11/ETH_TX_EN/I2C2_SDA/LTDC_G5/TIM2_CH4/USART3_RX/USB_OTG_HS_ULPI_D4/PB11_70") (pintype "bidirectional"))
      (node (ref "U19") (pin "3") (pinfunction "IN3_3") (pintype "unspecified"))
    )
    (net (code "9") (name "COOLING FAN 3") (class "Default")
      (node (ref "BRAIN") (pin "75") (pinfunction "SPI2_MISO/TIM12_CH1/TIM1_CH2N/TIM8_CH2N/USART3_RTS/USB_OTG_HS_DM/PB14_75") (pintype "bidirectional"))
      (node (ref "U19") (pin "2") (pinfunction "IN2_2") (pintype "unspecified"))
    )
    (net (code "10") (name "COOLING FAN 4") (class "Default")
      (node (ref "BRAIN") (pin "76") (pinfunction "I2S2_SD/RTC_REFIN/SPI2_MOSI/TIM12_CH2/TIM1_CH3N/TIM8_CH3N/USB_OTG_HS_DP/PB15_76") (pintype "bidirectional"))
      (node (ref "U19") (pin "1") (pinfunction "IN1_1") (pintype "unspecified"))
    )
    (net (code "11") (name "D4") (class "Default")
      (node (ref "BRAIN") (pin "100") (pinfunction "I2C3_SCL/LTDC_R6/RCC_MCO_1/TIM1_CH1/TIM8_BKIN2/USART1_CK/USB_OTG_FS_SOF/PA8_100") (pintype "bidirectional"))
      (node (ref "EXP1") (pin "6") (pinfunction "6_6") (pintype "unspecified"))
    )
    (net (code "12") (name "D5") (class "Default")
      (node (ref "BRAIN") (pin "110") (pinfunction "CEC/I2S1_WS/I2S3_WS/SPI1_NSS/SPI3_NSS/SYS_JTDI/TIM2_CH1/TIM2_ETR/UART4_RTS/PA15_110") (pintype "bidirectional"))
      (node (ref "EXP1") (pin "5") (pinfunction "5_5") (pintype "unspecified"))
    )
    (net (code "13") (name "D6") (class "Default")
      (node (ref "BRAIN") (pin "111") (pinfunction "DCMI_D8/I2S3_CK/LTDC_R2/QUADSPI_BK1_IO1/SDMMC1_D2/SPI3_SCK/UART4_TX/USART3_TX/PC10_111") (pintype "bidirectional"))
      (node (ref "EXP1") (pin "4") (pinfunction "4_4") (pintype "unspecified"))
    )
    (net (code "14") (name "D7") (class "Default")
      (node (ref "BRAIN") (pin "112") (pinfunction "ADC1_EXTI11/ADC2_EXTI11/ADC3_EXTI11/DCMI_D4/QUADSPI_BK2_NCS/SDMMC1_D3/SPI3_MISO/UART4_RX/USART3_RX/PC11_112") (pintype "bidirectional"))
      (node (ref "EXP1") (pin "3") (pinfunction "3_3") (pintype "unspecified"))
    )
    (net (code "15") (name "DIAGX") (class "Default")
      (node (ref "BRAIN") (pin "45") (pinfunction "ADC1_IN15/ADC2_IN15/ETH_RXD1/FMC_SDCKE0/SPDIFRX_IN3/PC5_45") (pintype "bidirectional"))
      (node (ref "U2") (pin "18") (pinfunction "DIAG_18") (pintype "unspecified"))
    )
    (net (code "16") (name "DIAGY") (class "Default")
      (node (ref "BRAIN") (pin "22") (pinfunction "PF10/ADC3_IN8/DCMI_D11/LTDC_DE_22") (pintype "bidirectional"))
      (node (ref "U3") (pin "18") (pinfunction "DIAG_18") (pintype "unspecified"))
    )
    (net (code "17") (name "DIAGZ1") (class "Default")
      (node (ref "BRAIN") (pin "14") (pinfunction "PF4/ADC3_IN14/FMC_A4_14") (pintype "bidirectional"))
      (node (ref "U4") (pin "18") (pinfunction "DIAG_18") (pintype "unspecified"))
    )
    (net (code "18") (name "DIAGZ2") (class "Default")
      (node (ref "BRAIN") (pin "8") (pinfunction "RCC_OSC32_IN/PC14_8") (pintype "bidirectional"))
      (node (ref "U5") (pin "18") (pinfunction "DIAG_18") (pintype "unspecified"))
    )
    (net (code "19") (name "E1DIAG") (class "Default")
      (node (ref "BRAIN") (pin "141") (pinfunction "PE0/DCMI_D2/FMC_NBL0/LPTIM1_ETR/SAI2_MCLK_A/TIM4_ETR/UART8_RX_141") (pintype "bidirectional"))
      (node (ref "U7") (pin "18") (pinfunction "DIAG_18") (pintype "unspecified"))
    )
    (net (code "20") (name "E1RX") (class "Default")
      (node (ref "BRAIN") (pin "139") (pinfunction "CAN1_RX/DCMI_D6/ETH_TXD3/I2C1_SCL/LTDC_B6/SDMMC1_D4/TIM10_CH1/TIM4_CH3/PB8_139") (pintype "bidirectional"))
      (node (ref "J48") (pin "2") (pinfunction "2_2") (pintype "unspecified"))
      (node (ref "U7") (pin "5") (pinfunction "RX_5") (pintype "unspecified"))
    )
    (net (code "21") (name "E1TX") (class "Default")
      (node (ref "BRAIN") (pin "140") (pinfunction "CAN1_TX/DAC_EXTI9/DCMI_D7/I2C1_SDA/I2S2_WS/LTDC_B7/SDMMC1_D5/SPI2_NSS/TIM11_CH1/TIM4_CH4/PB9_140") (pintype "bidirectional"))
      (node (ref "J36") (pin "6") (pinfunction "6_6") (pintype "input"))
      (node (ref "U7") (pin "4") (pinfunction "TX_4") (pintype "unspecified"))
    )
    (net (code "22") (name "E2DIAG") (class "Default")
      (node (ref "BRAIN") (pin "128") (pinfunction "PG13/ETH_TXD0/FMC_A24/LPTIM1_OUT/LTDC_R0/SPI6_SCK/SYS_TRACED0/USART6_CTS_128") (pintype "bidirectional"))
      (node (ref "U8") (pin "18") (pinfunction "DIAG_18") (pintype "unspecified"))
    )
    (net (code "23") (name "E2RX") (class "Default")
      (node (ref "BRAIN") (pin "124") (pinfunction "PG9/DAC_EXTI9/DCMI_VSYNC/FMC_NCE3/FMC_NE2/QUADSPI_BK2_IO2/SAI2_FS_B/SPDIFRX_IN3/USART6_RX_124") (pintype "bidirectional"))
      (node (ref "J49") (pin "2") (pinfunction "2_2") (pintype "unspecified"))
      (node (ref "U8") (pin "5") (pinfunction "RX_5") (pintype "unspecified"))
    )
    (net (code "24") (name "E2TX") (class "Default")
      (node (ref "BRAIN") (pin "123") (pinfunction "FMC_NE1/SPDIFRX_IN0/USART2_CK/PD7_123") (pintype "bidirectional"))
      (node (ref "J37") (pin "6") (pinfunction "6_6") (pintype "input"))
      (node (ref "U8") (pin "4") (pinfunction "TX_4") (pintype "unspecified"))
    )
    (net (code "25") (name "E3DIAG") (class "Default")
      (node (ref "BRAIN") (pin "122") (pinfunction "DCMI_D10/FMC_NWAIT/I2S3_SD/LTDC_B2/SAI1_SD_A/SPI3_MOSI/USART2_RX/PD6_122") (pintype "bidirectional"))
      (node (ref "U9") (pin "18") (pinfunction "DIAG_18") (pintype "unspecified"))
    )
    (net (code "26") (name "E3RX") (class "Default")
      (node (ref "BRAIN") (pin "119") (pinfunction "FMC_NWE/USART2_TX/PD5_119") (pintype "bidirectional"))
      (node (ref "J50") (pin "2") (pinfunction "2_2") (pintype "unspecified"))
      (node (ref "U9") (pin "5") (pinfunction "RX_5") (pintype "unspecified"))
    )
    (net (code "27") (name "E3TX") (class "Default")
      (node (ref "BRAIN") (pin "118") (pinfunction "FMC_NOE/USART2_RTS/PD4_118") (pintype "bidirectional"))
      (node (ref "J38") (pin "6") (pinfunction "6_6") (pintype "input"))
      (node (ref "U9") (pin "4") (pinfunction "TX_4") (pintype "unspecified"))
    )
    (net (code "28") (name "E4DIAG") (class "Default")
      (node (ref "BRAIN") (pin "93") (pinfunction "PG8/ETH_PPS_OUT/FMC_SDCLK/SPDIFRX_IN2/SPI6_NSS/USART6_RTS_93") (pintype "bidirectional"))
      (node (ref "U10") (pin "18") (pinfunction "DIAG_18") (pintype "unspecified"))
    )
    (net (code "29") (name "E4RX") (class "Default")
      (node (ref "BRAIN") (pin "90") (pinfunction "PG5/FMC_A15/FMC_BA1_90") (pintype "bidirectional"))
      (node (ref "J51") (pin "2") (pinfunction "2_2") (pintype "unspecified"))
      (node (ref "U10") (pin "5") (pinfunction "RX_5") (pintype "unspecified"))
    )
    (net (code "30") (name "E4TX") (class "Default")
      (node (ref "BRAIN") (pin "89") (pinfunction "PG4/FMC_A14/FMC_BA0_89") (pintype "bidirectional"))
      (node (ref "J39") (pin "6") (pinfunction "6_6") (pintype "input"))
      (node (ref "U10") (pin "4") (pinfunction "TX_4") (pintype "unspecified"))
    )
    (net (code "31") (name "EDIR1") (class "Default")
      (node (ref "BRAIN") (pin "132") (pinfunction "PG15/DCMI_D13/FMC_SDNCAS/USART6_CTS_132") (pintype "bidirectional"))
      (node (ref "U7") (pin "8") (pinfunction "DIR_8") (pintype "unspecified"))
    )
    (net (code "32") (name "EDIR2") (class "Default")
      (node (ref "BRAIN") (pin "125") (pinfunction "PG10/DCMI_D2/FMC_NE3/LTDC_B2/LTDC_G3/SAI2_SD_B_125") (pintype "bidirectional"))
      (node (ref "U8") (pin "8") (pinfunction "DIR_8") (pintype "unspecified"))
    )
    (net (code "33") (name "EDIR3") (class "Default")
      (node (ref "BRAIN") (pin "87") (pinfunction "PG2/FMC_A12_87") (pintype "bidirectional"))
      (node (ref "U9") (pin "8") (pinfunction "DIR_8") (pintype "unspecified"))
    )
    (net (code "34") (name "EDIR4") (class "Default")
      (node (ref "BRAIN") (pin "91") (pinfunction "PG6/DCMI_D12/LTDC_R7_91") (pintype "bidirectional"))
      (node (ref "U10") (pin "8") (pinfunction "DIR_8") (pintype "unspecified"))
    )
    (net (code "35") (name "EEN1") (class "Default")
      (node (ref "BRAIN") (pin "129") (pinfunction "PG14/ETH_TXD1/FMC_A25/LPTIM1_ETR/LTDC_B0/QUADSPI_BK2_IO3/SPI6_MOSI/SYS_TRACED1/USART6_TX_129") (pintype "bidirectional"))
      (node (ref "R5") (pin "2") (pinfunction "2_2") (pintype "unspecified"))
      (node (ref "U7") (pin "1") (pinfunction "EN_1") (pintype "unspecified"))
    )
    (net (code "36") (name "EEN2") (class "Default")
      (node (ref "BRAIN") (pin "126") (pinfunction "PG11/ADC1_EXTI11/ADC2_EXTI11/ADC3_EXTI11/DCMI_D3/ETH_TX_EN/LTDC_B3/SPDIFRX_IN0_126") (pintype "bidirectional"))
      (node (ref "R6") (pin "2") (pinfunction "2_2") (pintype "unspecified"))
      (node (ref "U8") (pin "1") (pinfunction "EN_1") (pintype "unspecified"))
    )
    (net (code "37") (name "EEN3") (class "Default")
      (node (ref "BRAIN") (pin "117") (pinfunction "DCMI_D5/FMC_CLK/I2S2_CK/LTDC_G7/SPI2_SCK/USART2_CTS/PD3_117") (pintype "bidirectional"))
      (node (ref "R8") (pin "2") (pinfunction "2_2") (pintype "unspecified"))
      (node (ref "U9") (pin "1") (pinfunction "EN_1") (pintype "unspecified"))
    )
    (net (code "38") (name "EEN4") (class "Default")
      (node (ref "BRAIN") (pin "88") (pinfunction "PG3/FMC_A13_88") (pintype "bidirectional"))
      (node (ref "R10") (pin "2") (pinfunction "2_2") (pintype "unspecified"))
      (node (ref "U10") (pin "1") (pinfunction "EN_1") (pintype "unspecified"))
    )
    (net (code "39") (name "EN") (class "Default")
      (node (ref "BRAIN") (pin "114") (pinfunction "CAN1_RX/FMC_D2/FMC_DA2/PD0_114") (pintype "bidirectional"))
      (node (ref "EXP1") (pin "8") (pinfunction "8_8") (pintype "unspecified"))
    )
    (net (code "40") (name "EN1") (class "Default")
      (node (ref "BRAIN") (pin "79") (pinfunction "FMC_D15/FMC_DA15/LTDC_B3/USART3_CK/PD10_79") (pintype "bidirectional"))
      (node (ref "EXP2") (pin "5") (pinfunction "5_5") (pintype "unspecified"))
    )
    (net (code "41") (name "EN2") (class "Default")
      (node (ref "BRAIN") (pin "78") (pinfunction "DAC_EXTI9/FMC_D14/FMC_DA14/USART3_RX/PD9_78") (pintype "bidirectional"))
      (node (ref "EXP2") (pin "3") (pinfunction "3_3") (pintype "unspecified"))
    )
    (net (code "42") (name "ENCBTN") (class "Default")
      (node (ref "BRAIN") (pin "115") (pinfunction "CAN1_TX/FMC_D3/FMC_DA3/PD1_115") (pintype "bidirectional"))
      (node (ref "EXP1") (pin "9") (pinfunction "9_9") (pintype "unspecified"))
    )
    (net (code "43") (name "ESTEP1") (class "Default")
      (node (ref "BRAIN") (pin "142") (pinfunction "PE1/DCMI_D3/FMC_NBL1/LPTIM1_IN2/UART8_TX_142") (pintype "bidirectional"))
      (node (ref "U7") (pin "7") (pinfunction "STEP_7") (pintype "unspecified"))
    )
    (net (code "44") (name "ESTEP2") (class "Default")
      (node (ref "BRAIN") (pin "127") (pinfunction "PG12/FMC_NE4/LPTIM1_IN1/LTDC_B1/LTDC_B4/SPDIFRX_IN1/SPI6_MISO/USART6_RTS_127") (pintype "bidirectional"))
      (node (ref "U8") (pin "7") (pinfunction "STEP_7") (pintype "unspecified"))
    )
    (net (code "45") (name "ESTEP3") (class "Default")
      (node (ref "BRAIN") (pin "80") (pinfunction "ADC1_EXTI11/ADC2_EXTI11/ADC3_EXTI11/FMC_A16/FMC_CLE/I2C4_SMBA/QUADSPI_BK1_IO0/SAI2_SD_A/USART3_CTS/PD11_80") (pintype "bidirectional"))
      (node (ref "U9") (pin "7") (pinfunction "STEP_7") (pintype "unspecified"))
    )
    (net (code "46") (name "ESTEP4") (class "Default")
      (node (ref "BRAIN") (pin "92") (pinfunction "PG7/DCMI_D13/FMC_INT3/LTDC_CLK/USART6_CK_92") (pintype "bidirectional"))
      (node (ref "U10") (pin "7") (pinfunction "STEP_7") (pintype "unspecified"))
    )
    (net (code "47") (name "FEND1") (class "Default")
      (node (ref "BRAIN") (pin "58") (pinfunction "PE7/FMC_D4/FMC_DA4/QUADSPI_BK2_IO0/TIM1_ETR/UART7_RX_58") (pintype "bidirectional"))
      (node (ref "FEND1") (pin "3") (pinfunction "3_3") (pintype "input"))
    )
    (net (code "48") (name "FEND2") (class "Default")
      (node (ref "BRAIN") (pin "59") (pinfunction "PE8/FMC_D5/FMC_DA5/QUADSPI_BK2_IO1/TIM1_CH1N/UART7_TX_59") (pintype "bidirectional"))
      (node (ref "FEND2") (pin "3") (pinfunction "3_3") (pintype "input"))
    )
    (net (code "49") (name "FEND3") (class "Default")
      (node (ref "BRAIN") (pin "63") (pinfunction "PE10/FMC_D7/FMC_DA7/QUADSPI_BK2_IO3/TIM1_CH2N/UART7_CTS_63") (pintype "bidirectional"))
      (node (ref "FEND3") (pin "3") (pinfunction "3_3") (pintype "input"))
    )
    (net (code "50") (name "FEND4") (class "Default")
      (node (ref "BRAIN") (pin "65") (pinfunction "PE12/FMC_D9/FMC_DA9/LTDC_B4/SAI2_SCK_B/SPI4_SCK/TIM1_CH3N_65") (pintype "bidirectional"))
      (node (ref "FEND4") (pin "3") (pinfunction "3_3") (pintype "input"))
    )
    (net (code "51") (name "GND") (class "Default")
      (node (ref "BLTOUCH") (pin "1") (pinfunction "1_1") (pintype "input"))
      (node (ref "BOOTSEL") (pin "3") (pinfunction "3_3") (pintype "unspecified"))
      (node (ref "BOOTSEL") (pin "4") (pinfunction "4_4") (pintype "unspecified"))
      (node (ref "BOOTSEL") (pin "5") (pinfunction "5_5") (pintype "unspecified"))
      (node (ref "BRAIN") (pin "107") (pinfunction "VSS_107") (pintype "bidirectional"))
      (node (ref "BRAIN") (pin "120") (pinfunction "VSS_120") (pintype "bidirectional"))
      (node (ref "BRAIN") (pin "130") (pinfunction "VSS_130") (pintype "bidirectional"))
      (node (ref "BRAIN") (pin "16") (pinfunction "VSS_16") (pintype "bidirectional"))
      (node (ref "BRAIN") (pin "31") (pinfunction "VSSA_31") (pintype "bidirectional"))
      (node (ref "BRAIN") (pin "38") (pinfunction "VSS_38") (pintype "bidirectional"))
      (node (ref "BRAIN") (pin "51") (pinfunction "VSS_51") (pintype "bidirectional"))
      (node (ref "BRAIN") (pin "61") (pinfunction "VSS_61") (pintype "bidirectional"))
      (node (ref "BRAIN") (pin "83") (pinfunction "VSS_83") (pintype "bidirectional"))
      (node (ref "BRAIN") (pin "94") (pinfunction "VSS_94") (pintype "bidirectional"))
      (node (ref "BUFFER") (pin "1") (pinfunction "GND_1") (pintype "unspecified"))
      (node (ref "C1") (pin "1") (pinfunction "1_1") (pintype "unspecified"))
      (node (ref "C10") (pin "1") (pinfunction "1_1") (pintype "unspecified"))
      (node (ref "C11") (pin "1") (pinfunction "1_1") (pintype "unspecified"))
      (node (ref "C12") (pin "1") (pinfunction "1_1") (pintype "unspecified"))
      (node (ref "C13") (pin "1") (pinfunction "1_1") (pintype "unspecified"))
      (node (ref "C14") (pin "1") (pinfunction "1_1") (pintype "unspecified"))
      (node (ref "C15") (pin "1") (pinfunction "1_1") (pintype "unspecified"))
      (node (ref "C16") (pin "1") (pinfunction "1_1") (pintype "unspecified"))
      (node (ref "C17") (pin "1") (pinfunction "1_1") (pintype "unspecified"))
      (node (ref "C18") (pin "1") (pinfunction "1_1") (pintype "unspecified"))
      (node (ref "C19") (pin "1") (pinfunction "1_1") (pintype "unspecified"))
      (node (ref "C2") (pin "1") (pinfunction "1_1") (pintype "unspecified"))
      (node (ref "C20") (pin "1") (pinfunction "1_1") (pintype "unspecified"))
      (node (ref "C21") (pin "1") (pinfunction "1_1") (pintype "unspecified"))
      (node (ref "C22") (pin "1") (pinfunction "1_1") (pintype "unspecified"))
      (node (ref "C23") (pin "2") (pinfunction "2_2") (pintype "unspecified"))
      (node (ref "C24") (pin "2") (pinfunction "2_2") (pintype "unspecified"))
      (node (ref "C3") (pin "1") (pinfunction "1_1") (pintype "unspecified"))
      (node (ref "C4") (pin "1") (pinfunction "1_1") (pintype "unspecified"))
      (node (ref "C5") (pin "1") (pinfunction "1_1") (pintype "unspecified"))
      (node (ref "C6") (pin "1") (pinfunction "1_1") (pintype "unspecified"))
      (node (ref "C7") (pin "1") (pinfunction "1_1") (pintype "unspecified"))
      (node (ref "C8") (pin "1") (pinfunction "1_1") (pintype "unspecified"))
      (node (ref "C9") (pin "1") (pinfunction "1_1") (pintype "unspecified"))
      (node (ref "EXP1") (pin "2") (pinfunction "2_2") (pintype "unspecified"))
      (node (ref "EXP2") (pin "9") (pinfunction "9_9") (pintype "unspecified"))
      (node (ref "FEND1") (pin "2") (pinfunction "2_2") (pintype "input"))
      (node (ref "FEND2") (pin "2") (pinfunction "2_2") (pintype "input"))
      (node (ref "FEND3") (pin "2") (pinfunction "2_2") (pintype "input"))
      (node (ref "FEND4") (pin "2") (pinfunction "2_2") (pintype "input"))
      (node (ref "I2C1") (pin "4") (pinfunction "4_4") (pintype "unspecified"))
      (node (ref "I2C2") (pin "4") (pinfunction "4_4") (pintype "unspecified"))
      (node (ref "I2C3") (pin "4") (pinfunction "4_4") (pintype "unspecified"))
      (node (ref "I2C4") (pin "4") (pinfunction "4_4") (pintype "unspecified"))
      (node (ref "I2C5") (pin "4") (pinfunction "4_4") (pintype "unspecified"))
      (node (ref "J1") (pin "10") (pinfunction "10_10") (pintype "unspecified"))
      (node (ref "J1") (pin "12") (pinfunction "12_12") (pintype "unspecified"))
      (node (ref "J1") (pin "2") (pinfunction "2_2") (pintype "unspecified"))
      (node (ref "J1") (pin "4") (pinfunction "4_4") (pintype "unspecified"))
      (node (ref "J1") (pin "6") (pinfunction "6_6") (pintype "unspecified"))
      (node (ref "J1") (pin "8") (pinfunction "8_8") (pintype "unspecified"))
      (node (ref "J8") (pin "1") (pinfunction "1_1") (pintype "input"))
      (node (ref "LED17") (pin "2") (pinfunction "2_2") (pintype "unspecified"))
      (node (ref "NEXTION") (pin "4") (pinfunction "4_4") (pintype "unspecified"))
      (node (ref "P11") (pin "1") (pinfunction "1_1") (pintype "unspecified"))
      (node (ref "P2") (pin "2") (pinfunction "2_2") (pintype "unspecified"))
      (node (ref "P3") (pin "2") (pinfunction "2_2") (pintype "unspecified"))
      (node (ref "P5") (pin "2") (pinfunction "2_2") (pintype "unspecified"))
      (node (ref "P6") (pin "1") (pinfunction "1_1") (pintype "unspecified"))
      (node (ref "P8") (pin "2") (pinfunction "2_2") (pintype "unspecified"))
      (node (ref "PROBE") (pin "2") (pinfunction "2_2") (pintype "input"))
      (node (ref "Q1") (pin "3") (pinfunction "S_3") (pintype "unspecified"))
      (node (ref "Q2") (pin "3") (pinfunction "S_3") (pintype "unspecified"))
      (node (ref "Q3") (pin "3") (pinfunction "S_3") (pintype "unspecified"))
      (node (ref "Q4") (pin "3") (pinfunction "S_3") (pintype "unspecified"))
      (node (ref "Q5") (pin "1") (pinfunction "G_1") (pintype "input"))
      (node (ref "Q6") (pin "3") (pinfunction "S_3") (pintype "unspecified"))
      (node (ref "Q7") (pin "3") (pinfunction "S_3") (pintype "unspecified"))
      (node (ref "R17") (pin "2") (pinfunction "2_2") (pintype "unspecified"))
      (node (ref "R20") (pin "2") (pinfunction "2_2") (pintype "unspecified"))
      (node (ref "R22") (pin "2") (pinfunction "2_2") (pintype "unspecified"))
      (node (ref "R24") (pin "2") (pinfunction "2_2") (pintype "unspecified"))
      (node (ref "R32") (pin "1") (pinfunction "1_1") (pintype "unspecified"))
      (node (ref "R41") (pin "2") (pinfunction "2_2") (pintype "unspecified"))
      (node (ref "R42") (pin "2") (pinfunction "2_2") (pintype "unspecified"))
      (node (ref "R49") (pin "2") (pinfunction "2_2") (pintype "unspecified"))
      (node (ref "RESET") (pin "1") (pinfunction "1_1") (pintype "unspecified"))
      (node (ref "RESET") (pin "2") (pinfunction "2_2") (pintype "unspecified"))
      (node (ref "RXLED") (pin "2") (pinfunction "2_2") (pintype "unspecified"))
      (node (ref "SDCARD") (pin "11") (pinfunction "SHIELD_11") (pintype "unspecified"))
      (node (ref "SDCARD") (pin "6") (pinfunction "GND_6") (pintype "bidirectional"))
      (node (ref "SDCARD") (pin "9") (pinfunction "DET_B_9") (pintype "unspecified"))
      (node (ref "SERVO1") (pin "1") (pinfunction "1_1") (pintype "input"))
      (node (ref "SERVO2") (pin "1") (pinfunction "1_1") (pintype "input"))
      (node (ref "TXLED") (pin "2") (pinfunction "2_2") (pintype "unspecified"))
      (node (ref "U1") (pin "2") (pinfunction "IN-_2") (pintype "unspecified"))
      (node (ref "U1") (pin "4") (pinfunction "OUT-_4") (pintype "unspecified"))
      (node (ref "U10") (pin "15") (pinfunction "GND_15") (pintype "unspecified"))
      (node (ref "U10") (pin "9") (pinfunction "GND_9") (pintype "unspecified"))
      (node (ref "U15") (pin "2") (pinfunction "IN-_2") (pintype "unspecified"))
      (node (ref "U15") (pin "4") (pinfunction "OUT-_4") (pintype "unspecified"))
      (node (ref "U18") (pin "8") (pinfunction "GND_8") (pintype "unspecified"))
      (node (ref "U19") (pin "8") (pinfunction "GND_8") (pintype "unspecified"))
      (node (ref "U2") (pin "15") (pinfunction "GND_15") (pintype "unspecified"))
      (node (ref "U2") (pin "9") (pinfunction "GND_9") (pintype "unspecified"))
      (node (ref "U3") (pin "15") (pinfunction "GND_15") (pintype "unspecified"))
      (node (ref "U4") (pin "15") (pinfunction "GND_15") (pintype "unspecified"))
      (node (ref "U4") (pin "9") (pinfunction "GND_9") (pintype "unspecified"))
      (node (ref "U5") (pin "15") (pinfunction "GND_15") (pintype "unspecified"))
      (node (ref "U5") (pin "9") (pinfunction "GND_9") (pintype "unspecified"))
      (node (ref "U6") (pin "1") (pinfunction "ADJ(GND)_1") (pintype "unspecified"))
      (node (ref "U7") (pin "15") (pinfunction "GND_15") (pintype "unspecified"))
      (node (ref "U7") (pin "9") (pinfunction "GND_9") (pintype "unspecified"))
      (node (ref "U8") (pin "15") (pinfunction "GND_15") (pintype "unspecified"))
      (node (ref "U8") (pin "9") (pinfunction "GND_9") (pintype "unspecified"))
      (node (ref "U9") (pin "15") (pinfunction "GND_15") (pintype "unspecified"))
      (node (ref "U9") (pin "9") (pinfunction "GND_9") (pintype "unspecified"))
      (node (ref "USB") (pin "4") (pinfunction "4_4") (pintype "bidirectional"))
      (node (ref "USB") (pin "S1") (pinfunction "SHIELD_S1") (pintype "bidirectional"))
      (node (ref "USB") (pin "S2") (pinfunction "SHIELD_S2") (pintype "bidirectional"))
      (node (ref "USB_OTG") (pin "4") (pinfunction "4_4") (pintype "bidirectional"))
      (node (ref "USB_OTG") (pin "S1") (pinfunction "SHIELD_S1") (pintype "bidirectional"))
      (node (ref "USB_OTG") (pin "S2") (pinfunction "SHIELD_S2") (pintype "bidirectional"))
      (node (ref "USB_SER") (pin "20") (pinfunction "VSS_20") (pintype "unspecified"))
      (node (ref "XMAX") (pin "2") (pinfunction "2_2") (pintype "input"))
      (node (ref "XMIN") (pin "2") (pinfunction "2_2") (pintype "input"))
      (node (ref "YMAX") (pin "2") (pinfunction "2_2") (pintype "input"))
      (node (ref "YMIN") (pin "2") (pinfunction "2_2") (pintype "input"))
      (node (ref "Z1MAX") (pin "2") (pinfunction "2_2") (pintype "input"))
      (node (ref "Z1MIN") (pin "2") (pinfunction "2_2") (pintype "input"))
      (node (ref "Z2MAX") (pin "2") (pinfunction "2_2") (pintype "input"))
      (node (ref "Z2MIN") (pin "2") (pinfunction "2_2") (pintype "input"))
    )
    (net (code "52") (name "HEATER1") (class "Default")
      (node (ref "BRAIN") (pin "60") (pinfunction "PE9/DAC_EXTI9/FMC_D6/FMC_DA6/QUADSPI_BK2_IO2/TIM1_CH1/UART7_RTS_60") (pintype "bidirectional"))
      (node (ref "R11") (pin "1") (pinfunction "1_1") (pintype "unspecified"))
      (node (ref "R17") (pin "1") (pinfunction "1_1") (pintype "unspecified"))
    )
    (net (code "53") (name "HEATER2") (class "Default")
      (node (ref "BRAIN") (pin "64") (pinfunction "PE11/ADC1_EXTI11/ADC2_EXTI11/ADC3_EXTI11/FMC_D8/FMC_DA8/LTDC_G3/SAI2_SD_B/SPI4_NSS/TIM1_CH2_64") (pintype "bidirectional"))
      (node (ref "R12") (pin "1") (pinfunction "1_1") (pintype "unspecified"))
      (node (ref "R20") (pin "1") (pinfunction "1_1") (pintype "unspecified"))
    )
    (net (code "54") (name "HEATER3") (class "Default")
      (node (ref "BRAIN") (pin "66") (pinfunction "PE13/FMC_D10/FMC_DA10/LTDC_DE/SAI2_FS_B/SPI4_MISO/TIM1_CH3_66") (pintype "bidirectional"))
      (node (ref "R13") (pin "1") (pinfunction "1_1") (pintype "unspecified"))
      (node (ref "R22") (pin "1") (pinfunction "1_1") (pintype "unspecified"))
    )
    (net (code "55") (name "HEATER4") (class "Default")
      (node (ref "BRAIN") (pin "67") (pinfunction "PE14/FMC_D11/FMC_DA11/LTDC_CLK/SAI2_MCLK_B/SPI4_MOSI/TIM1_CH4_67") (pintype "bidirectional"))
      (node (ref "R14") (pin "1") (pinfunction "1_1") (pintype "unspecified"))
      (node (ref "R24") (pin "1") (pinfunction "1_1") (pintype "unspecified"))
    )
    (net (code "56") (name "I2CSCL") (class "Default")
      (node (ref "BRAIN") (pin "136") (pinfunction "CAN2_TX/CEC/DCMI_D5/FMC_SDNE1/I2C1_SCL/QUADSPI_BK1_NCS/TIM4_CH1/USART1_TX/PB6_136") (pintype "bidirectional"))
      (node (ref "I2C1") (pin "2") (pinfunction "2_2") (pintype "unspecified"))
      (node (ref "I2C2") (pin "2") (pinfunction "2_2") (pintype "unspecified"))
      (node (ref "I2C3") (pin "2") (pinfunction "2_2") (pintype "unspecified"))
      (node (ref "I2C4") (pin "2") (pinfunction "2_2") (pintype "unspecified"))
      (node (ref "I2C5") (pin "2") (pinfunction "2_2") (pintype "unspecified"))
      (node (ref "R53") (pin "1") (pinfunction "1_1") (pintype "unspecified"))
    )
    (net (code "57") (name "I2CSDA") (class "Default")
      (node (ref "BRAIN") (pin "137") (pinfunction "DCMI_VSYNC/FMC_NL/I2C1_SDA/TIM4_CH2/USART1_RX/PB7_137") (pintype "bidirectional"))
      (node (ref "I2C1") (pin "1") (pinfunction "1_1") (pintype "unspecified"))
      (node (ref "I2C2") (pin "1") (pinfunction "1_1") (pintype "unspecified"))
      (node (ref "I2C3") (pin "1") (pinfunction "1_1") (pintype "unspecified"))
      (node (ref "I2C4") (pin "1") (pinfunction "1_1") (pintype "unspecified"))
      (node (ref "I2C5") (pin "1") (pinfunction "1_1") (pintype "unspecified"))
      (node (ref "R52") (pin "1") (pinfunction "1_1") (pintype "unspecified"))
    )
    (net (code "58") (name "KILL") (class "Default")
      (node (ref "BRAIN") (pin "77") (pinfunction "FMC_D13/FMC_DA13/SPDIFRX_IN1/USART3_TX/PD8_77") (pintype "bidirectional"))
      (node (ref "EXP2") (pin "10") (pinfunction "10_10") (pintype "unspecified"))
    )
    (net (code "59") (name "MISO") (class "Default")
      (node (ref "BRAIN") (pin "134") (pinfunction "I2S2_WS/SPI1_MISO/SPI2_NSS/SPI3_MISO/SYS_JTRST/TIM3_CH1/PB4_134") (pintype "bidirectional"))
      (node (ref "EXP2") (pin "1") (pinfunction "1_1") (pintype "unspecified"))
      (node (ref "R29") (pin "1") (pinfunction "1_1") (pintype "unspecified"))
      (node (ref "SDCARD") (pin "7") (pinfunction "MISO_7") (pintype "input"))
    )
    (net (code "60") (name "MOSI") (class "Default")
      (node (ref "BRAIN") (pin "135") (pinfunction "CAN2_RX/DCMI_D10/ETH_PPS_OUT/FMC_SDCKE1/I2C1_SMBA/I2S1_SD/I2S3_SD/SPI1_MOSI/SPI3_MOSI/TIM3_CH2/USB_OTG_HS_ULPI_D7/PB5_135") (pintype "bidirectional"))
      (node (ref "EXP2") (pin "6") (pinfunction "6_6") (pintype "unspecified"))
      (node (ref "R30") (pin "1") (pinfunction "1_1") (pintype "unspecified"))
      (node (ref "SDCARD") (pin "3") (pinfunction "MOSI_3") (pintype "input"))
    )
    (net (code "61") (name "MOTOR") (class "Default")
      (node (ref "P5") (pin "1") (pinfunction "1_1") (pintype "unspecified"))
      (node (ref "P6") (pin "2") (pinfunction "2_2") (pintype "unspecified"))
      (node (ref "U10") (pin "16") (pinfunction "VM_16") (pintype "unspecified"))
      (node (ref "U2") (pin "16") (pinfunction "VM_16") (pintype "unspecified"))
      (node (ref "U3") (pin "16") (pinfunction "VM_16") (pintype "unspecified"))
      (node (ref "U4") (pin "16") (pinfunction "VM_16") (pintype "unspecified"))
      (node (ref "U5") (pin "16") (pinfunction "VM_16") (pintype "unspecified"))
      (node (ref "U7") (pin "16") (pinfunction "VM_16") (pintype "unspecified"))
      (node (ref "U8") (pin "16") (pinfunction "VM_16") (pintype "unspecified"))
      (node (ref "U9") (pin "16") (pinfunction "VM_16") (pintype "unspecified"))
    )
    (net (code "62") (name "Net-(BRAIN-BOOT0)") (class "Default")
      (node (ref "BOOTSEL") (pin "2") (pinfunction "2_2") (pintype "unspecified"))
      (node (ref "BRAIN") (pin "138") (pinfunction "BOOT0_138") (pintype "input"))
    )
    (net (code "63") (name "Net-(BRAIN-PDR_ON)") (class "Default")
      (node (ref "BRAIN") (pin "143") (pinfunction "PDR_ON_143") (pintype "input"))
      (node (ref "R48") (pin "2") (pinfunction "2_2") (pintype "unspecified"))
      (node (ref "R49") (pin "1") (pinfunction "1_1") (pintype "unspecified"))
    )
    (net (code "64") (name "Net-(BRAIN-PH0{slash}RCC_OSC_IN)") (class "Default")
      (node (ref "BRAIN") (pin "23") (pinfunction "PH0/RCC_OSC_IN_23") (pintype "input"))
      (node (ref "C17") (pin "2") (pinfunction "2_2") (pintype "unspecified"))
      (node (ref "X1") (pin "1") (pinfunction "OSC1_1") (pintype "input"))
    )
    (net (code "65") (name "Net-(BRAIN-PH1{slash}RCC_OSC_OUT)") (class "Default")
      (node (ref "BRAIN") (pin "24") (pinfunction "PH1/RCC_OSC_OUT_24") (pintype "input"))
      (node (ref "C18") (pin "2") (pinfunction "2_2") (pintype "unspecified"))
      (node (ref "X1") (pin "2") (pinfunction "OSC2_2") (pintype "input"))
    )
    (net (code "66") (name "Net-(BRAIN-VBAT)") (class "Default")
      (node (ref "BRAIN") (pin "6") (pinfunction "VBAT_6") (pintype "bidirectional"))
      (node (ref "Q5") (pin "2") (pinfunction "S_2") (pintype "unspecified"))
    )
    (net (code "67") (name "Net-(BRAIN-VCAP_1)") (class "Default")
      (node (ref "BRAIN") (pin "71") (pinfunction "VCAP_1_71") (pintype "bidirectional"))
      (node (ref "C19") (pin "2") (pinfunction "2_2") (pintype "unspecified"))
    )
    (net (code "68") (name "Net-(BRAIN-VCAP_2)") (class "Default")
      (node (ref "BRAIN") (pin "106") (pinfunction "VCAP_2_106") (pintype "bidirectional"))
      (node (ref "C20") (pin "2") (pinfunction "2_2") (pintype "unspecified"))
    )
    (net (code "69") (name "Net-(BUFFER-+)") (class "Default")
      (node (ref "BUFFER") (pin "2") (pinfunction "+_2") (pintype "unspecified"))
      (node (ref "Q5") (pin "3") (pinfunction "D_3") (pintype "unspecified"))
    )
    (net (code "70") (name "Net-(FUSE_BED-Pad1)") (class "Default")
      (node (ref "FUSE_BED") (pin "1") (pinfunction "1_1") (pintype "unspecified"))
      (node (ref "P1") (pin "1") (pinfunction "1_1") (pintype "unspecified"))
      (node (ref "R40") (pin "2") (pinfunction "2_2") (pintype "unspecified"))
    )
    (net (code "71") (name "Net-(FUSE_BED-Pad2)") (class "Default")
      (node (ref "FUSE_BED") (pin "2") (pinfunction "2_2") (pintype "unspecified"))
      (node (ref "P2") (pin "1") (pinfunction "1_1") (pintype "unspecified"))
    )
    (net (code "72") (name "Net-(FUSE_CHAMBER-Pad1)") (class "Default")
      (node (ref "FUSE_CHAMBER") (pin "1") (pinfunction "1_1") (pintype "unspecified"))
      (node (ref "P4") (pin "1") (pinfunction "1_1") (pintype "unspecified"))
      (node (ref "R43") (pin "2") (pinfunction "2_2") (pintype "unspecified"))
    )
    (net (code "73") (name "Net-(FUSE_CHAMBER-Pad2)") (class "Default")
      (node (ref "FUSE_CHAMBER") (pin "2") (pinfunction "2_2") (pintype "unspecified"))
      (node (ref "P3") (pin "1") (pinfunction "1_1") (pintype "unspecified"))
    )
    (net (code "74") (name "Net-(FUSE_HEAT-Pad2)") (class "Default")
      (node (ref "FUSE_HEAT") (pin "2") (pinfunction "2_2") (pintype "unspecified"))
      (node (ref "P8") (pin "1") (pinfunction "1_1") (pintype "unspecified"))
    )
    (net (code "75") (name "Net-(J55-Pad1)") (class "Default")
      (node (ref "J55") (pin "1") (pinfunction "1_1") (pintype "unspecified"))
      (node (ref "R47") (pin "2") (pinfunction "2_2") (pintype "unspecified"))
    )
    (net (code "76") (name "Net-(LED1-Pad1)") (class "Default")
      (node (ref "LED1") (pin "1") (pinfunction "1_1") (pintype "unspecified"))
      (node (ref "R18") (pin "1") (pinfunction "1_1") (pintype "unspecified"))
    )
    (net (code "77") (name "Net-(LED2-Pad1)") (class "Default")
      (node (ref "LED2") (pin "1") (pinfunction "1_1") (pintype "unspecified"))
      (node (ref "R19") (pin "1") (pinfunction "1_1") (pintype "unspecified"))
    )
    (net (code "78") (name "Net-(LED3-Pad1)") (class "Default")
      (node (ref "LED3") (pin "1") (pinfunction "1_1") (pintype "unspecified"))
      (node (ref "R21") (pin "1") (pinfunction "1_1") (pintype "unspecified"))
    )
    (net (code "79") (name "Net-(LED4-Pad1)") (class "Default")
      (node (ref "LED4") (pin "1") (pinfunction "1_1") (pintype "unspecified"))
      (node (ref "R23") (pin "1") (pinfunction "1_1") (pintype "unspecified"))
    )
    (net (code "80") (name "Net-(LED5-Pad1)") (class "Default")
      (node (ref "LED5") (pin "1") (pinfunction "1_1") (pintype "unspecified"))
      (node (ref "R40") (pin "1") (pinfunction "1_1") (pintype "unspecified"))
    )
    (net (code "81") (name "Net-(LED6-Pad1)") (class "Default")
      (node (ref "LED6") (pin "1") (pinfunction "1_1") (pintype "unspecified"))
      (node (ref "R43") (pin "1") (pinfunction "1_1") (pintype "unspecified"))
    )
    (net (code "82") (name "Net-(LED9-Pad1)") (class "Default")
      (node (ref "LED9") (pin "1") (pinfunction "1_1") (pintype "unspecified"))
      (node (ref "R34") (pin "1") (pinfunction "1_1") (pintype "unspecified"))
    )
    (net (code "83") (name "Net-(LED10-Pad1)") (class "Default")
      (node (ref "LED10") (pin "1") (pinfunction "1_1") (pintype "unspecified"))
      (node (ref "R36") (pin "1") (pinfunction "1_1") (pintype "unspecified"))
    )
    (net (code "84") (name "Net-(LED11-Pad1)") (class "Default")
      (node (ref "LED11") (pin "1") (pinfunction "1_1") (pintype "unspecified"))
      (node (ref "R38") (pin "1") (pinfunction "1_1") (pintype "unspecified"))
    )
    (net (code "85") (name "Net-(LED12-Pad1)") (class "Default")
      (node (ref "LED12") (pin "1") (pinfunction "1_1") (pintype "unspecified"))
      (node (ref "R39") (pin "1") (pinfunction "1_1") (pintype "unspecified"))
    )
    (net (code "86") (name "Net-(LED13-Pad1)") (class "Default")
      (node (ref "LED13") (pin "1") (pinfunction "1_1") (pintype "unspecified"))
      (node (ref "R54") (pin "1") (pinfunction "1_1") (pintype "unspecified"))
    )
    (net (code "87") (name "Net-(LED14-Pad1)") (class "Default")
      (node (ref "LED14") (pin "1") (pinfunction "1_1") (pintype "unspecified"))
      (node (ref "R55") (pin "1") (pinfunction "1_1") (pintype "unspecified"))
    )
    (net (code "88") (name "Net-(LED15-Pad1)") (class "Default")
      (node (ref "LED15") (pin "1") (pinfunction "1_1") (pintype "unspecified"))
      (node (ref "R57") (pin "1") (pinfunction "1_1") (pintype "unspecified"))
    )
    (net (code "89") (name "Net-(LED16-Pad1)") (class "Default")
      (node (ref "LED16") (pin "1") (pinfunction "1_1") (pintype "unspecified"))
      (node (ref "R59") (pin "1") (pinfunction "1_1") (pintype "unspecified"))
    )
    (net (code "90") (name "Net-(LED17-Pad1)") (class "Default")
      (node (ref "LED17") (pin "1") (pinfunction "1_1") (pintype "unspecified"))
      (node (ref "R47") (pin "1") (pinfunction "1_1") (pintype "unspecified"))
    )
    (net (code "91") (name "Net-(Q1-D)") (class "Default")
      (node (ref "LED1") (pin "2") (pinfunction "2_2") (pintype "unspecified"))
      (node (ref "P15") (pin "2") (pinfunction "2_2") (pintype "unspecified"))
      (node (ref "Q1") (pin "2") (pinfunction "D_2") (pintype "unspecified"))
    )
    (net (code "92") (name "Net-(Q1-G)") (class "Default")
      (node (ref "Q1") (pin "1") (pinfunction "G_1") (pintype "unspecified"))
      (node (ref "R11") (pin "2") (pinfunction "2_2") (pintype "unspecified"))
    )
    (net (code "93") (name "Net-(Q2-D)") (class "Default")
      (node (ref "LED2") (pin "2") (pinfunction "2_2") (pintype "unspecified"))
      (node (ref "P14") (pin "2") (pinfunction "2_2") (pintype "unspecified"))
      (node (ref "Q2") (pin "2") (pinfunction "D_2") (pintype "unspecified"))
    )
    (net (code "94") (name "Net-(Q2-G)") (class "Default")
      (node (ref "Q2") (pin "1") (pinfunction "G_1") (pintype "unspecified"))
      (node (ref "R12") (pin "2") (pinfunction "2_2") (pintype "unspecified"))
    )
    (net (code "95") (name "Net-(Q3-D)") (class "Default")
      (node (ref "LED3") (pin "2") (pinfunction "2_2") (pintype "unspecified"))
      (node (ref "P13") (pin "2") (pinfunction "2_2") (pintype "unspecified"))
      (node (ref "Q3") (pin "2") (pinfunction "D_2") (pintype "unspecified"))
    )
    (net (code "96") (name "Net-(Q3-G)") (class "Default")
      (node (ref "Q3") (pin "1") (pinfunction "G_1") (pintype "unspecified"))
      (node (ref "R13") (pin "2") (pinfunction "2_2") (pintype "unspecified"))
    )
    (net (code "97") (name "Net-(Q4-D)") (class "Default")
      (node (ref "LED4") (pin "2") (pinfunction "2_2") (pintype "unspecified"))
      (node (ref "P12") (pin "2") (pinfunction "2_2") (pintype "unspecified"))
      (node (ref "Q4") (pin "2") (pinfunction "D_2") (pintype "unspecified"))
    )
    (net (code "98") (name "Net-(Q4-G)") (class "Default")
      (node (ref "Q4") (pin "1") (pinfunction "G_1") (pintype "unspecified"))
      (node (ref "R14") (pin "2") (pinfunction "2_2") (pintype "unspecified"))
    )
    (net (code "99") (name "Net-(Q6-D)") (class "Default")
      (node (ref "LED5") (pin "2") (pinfunction "2_2") (pintype "unspecified"))
      (node (ref "P1") (pin "2") (pinfunction "2_2") (pintype "unspecified"))
      (node (ref "Q6") (pin "2") (pinfunction "D_2") (pintype "unspecified"))
    )
    (net (code "100") (name "Net-(Q6-G)") (class "Default")
      (node (ref "Q6") (pin "1") (pinfunction "G_1") (pintype "unspecified"))
      (node (ref "R37") (pin "2") (pinfunction "2_2") (pintype "unspecified"))
    )
    (net (code "101") (name "Net-(Q7-D)") (class "Default")
      (node (ref "LED6") (pin "2") (pinfunction "2_2") (pintype "unspecified"))
      (node (ref "P4") (pin "2") (pinfunction "2_2") (pintype "unspecified"))
      (node (ref "Q7") (pin "2") (pinfunction "D_2") (pintype "unspecified"))
    )
    (net (code "102") (name "Net-(Q7-G)") (class "Default")
      (node (ref "Q7") (pin "1") (pinfunction "G_1") (pintype "unspecified"))
      (node (ref "R44") (pin "2") (pinfunction "2_2") (pintype "unspecified"))
    )
    (net (code "103") (name "Net-(R27-Pad1)") (class "Default")
      (node (ref "R27") (pin "1") (pinfunction "1_1") (pintype "unspecified"))
      (node (ref "TXLED") (pin "1") (pinfunction "1_1") (pintype "unspecified"))
    )
    (net (code "104") (name "Net-(R33-Pad2)") (class "Default")
      (node (ref "R33") (pin "2") (pinfunction "2_2") (pintype "unspecified"))
      (node (ref "USB_OTG") (pin "2") (pinfunction "2_2") (pintype "bidirectional"))
    )
    (net (code "105") (name "Net-(R35-Pad2)") (class "Default")
      (node (ref "R35") (pin "2") (pinfunction "2_2") (pintype "unspecified"))
      (node (ref "USB_OTG") (pin "3") (pinfunction "3_3") (pintype "bidirectional"))
    )
    (net (code "106") (name "Net-(R45-Pad1)") (class "Default")
      (node (ref "R45") (pin "1") (pinfunction "1_1") (pintype "unspecified"))
      (node (ref "RXLED") (pin "1") (pinfunction "1_1") (pintype "unspecified"))
    )
    (net (code "107") (name "Net-(SDCARD-CS)") (class "Default")
      (node (ref "R31") (pin "1") (pinfunction "1_1") (pintype "unspecified"))
      (node (ref "R56") (pin "1") (pinfunction "1_1") (pintype "unspecified"))
      (node (ref "R60") (pin "2") (pinfunction "2_2") (pintype "unspecified"))
      (node (ref "SDCARD") (pin "2") (pinfunction "CS_2") (pintype "bidirectional"))
    )
    (net (code "108") (name "Net-(SDCARD-DET_A)") (class "Default")
      (node (ref "R58") (pin "2") (pinfunction "2_2") (pintype "unspecified"))
      (node (ref "R61") (pin "2") (pinfunction "2_2") (pintype "unspecified"))
      (node (ref "SDCARD") (pin "10") (pinfunction "DET_A_10") (pintype "unspecified"))
    )
    (net (code "109") (name "Net-(U1-IN+)") (class "Default")
      (node (ref "FUSE_24V") (pin "1") (pinfunction "1_1") (pintype "unspecified"))
      (node (ref "P11") (pin "2") (pinfunction "2_2") (pintype "unspecified"))
      (node (ref "U1") (pin "1") (pinfunction "IN+_1") (pintype "unspecified"))
    )
    (net (code "110") (name "Net-(U1-OUT+)") (class "Default")
      (node (ref "FUSE_5V") (pin "2") (pinfunction "2_2") (pintype "unspecified"))
      (node (ref "U1") (pin "3") (pinfunction "OUT+_3") (pintype "unspecified"))
    )
    (net (code "111") (name "Net-(U2-A1)") (class "Default")
      (node (ref "CN6") (pin "2") (pinfunction "2_2") (pintype "unspecified"))
      (node (ref "U2") (pin "13") (pinfunction "A1_13") (pintype "unspecified"))
    )
    (net (code "112") (name "Net-(U2-A2)") (class "Default")
      (node (ref "CN6") (pin "1") (pinfunction "1_1") (pintype "unspecified"))
      (node (ref "U2") (pin "14") (pinfunction "A2_14") (pintype "unspecified"))
    )
    (net (code "113") (name "Net-(U2-B1)") (class "Default")
      (node (ref "CN6") (pin "3") (pinfunction "3_3") (pintype "unspecified"))
      (node (ref "U2") (pin "12") (pinfunction "B1_12") (pintype "unspecified"))
    )
    (net (code "114") (name "Net-(U2-B2)") (class "Default")
      (node (ref "CN6") (pin "4") (pinfunction "4_4") (pintype "unspecified"))
      (node (ref "U2") (pin "11") (pinfunction "B2_11") (pintype "unspecified"))
    )
    (net (code "115") (name "Net-(U2-CLK)") (class "Default")
      (node (ref "J47") (pin "1") (pinfunction "1_1") (pintype "unspecified"))
      (node (ref "U2") (pin "6") (pinfunction "CLK_6") (pintype "unspecified"))
    )
    (net (code "116") (name "Net-(U2-MS1)") (class "Default")
      (node (ref "J40") (pin "2") (pinfunction "2_2") (pintype "input"))
      (node (ref "U2") (pin "2") (pinfunction "MS1_2") (pintype "unspecified"))
    )
    (net (code "117") (name "Net-(U2-MS2)") (class "Default")
      (node (ref "J40") (pin "4") (pinfunction "4_4") (pintype "input"))
      (node (ref "U2") (pin "3") (pinfunction "MS2_3") (pintype "unspecified"))
    )
    (net (code "118") (name "Net-(U3-A1)") (class "Default")
      (node (ref "CN5") (pin "2") (pinfunction "2_2") (pintype "unspecified"))
      (node (ref "U3") (pin "13") (pinfunction "A1_13") (pintype "unspecified"))
    )
    (net (code "119") (name "Net-(U3-A2)") (class "Default")
      (node (ref "CN5") (pin "1") (pinfunction "1_1") (pintype "unspecified"))
      (node (ref "U3") (pin "14") (pinfunction "A2_14") (pintype "unspecified"))
    )
    (net (code "120") (name "Net-(U3-B1)") (class "Default")
      (node (ref "CN5") (pin "3") (pinfunction "3_3") (pintype "unspecified"))
      (node (ref "U3") (pin "12") (pinfunction "B1_12") (pintype "unspecified"))
    )
    (net (code "121") (name "Net-(U3-B2)") (class "Default")
      (node (ref "CN5") (pin "4") (pinfunction "4_4") (pintype "unspecified"))
      (node (ref "U3") (pin "11") (pinfunction "B2_11") (pintype "unspecified"))
    )
    (net (code "122") (name "Net-(U3-CLK)") (class "Default")
      (node (ref "J46") (pin "1") (pinfunction "1_1") (pintype "unspecified"))
      (node (ref "U3") (pin "6") (pinfunction "CLK_6") (pintype "unspecified"))
    )
    (net (code "123") (name "Net-(U3-MS1)") (class "Default")
      (node (ref "J41") (pin "2") (pinfunction "2_2") (pintype "input"))
      (node (ref "U3") (pin "2") (pinfunction "MS1_2") (pintype "unspecified"))
    )
    (net (code "124") (name "Net-(U3-MS2)") (class "Default")
      (node (ref "J41") (pin "4") (pinfunction "4_4") (pintype "input"))
      (node (ref "U3") (pin "3") (pinfunction "MS2_3") (pintype "unspecified"))
    )
    (net (code "125") (name "Net-(U4-A1)") (class "Default")
      (node (ref "CN4") (pin "2") (pinfunction "2_2") (pintype "unspecified"))
      (node (ref "U4") (pin "13") (pinfunction "A1_13") (pintype "unspecified"))
    )
    (net (code "126") (name "Net-(U4-A2)") (class "Default")
      (node (ref "CN4") (pin "1") (pinfunction "1_1") (pintype "unspecified"))
      (node (ref "U4") (pin "14") (pinfunction "A2_14") (pintype "unspecified"))
    )
    (net (code "127") (name "Net-(U4-B1)") (class "Default")
      (node (ref "CN4") (pin "3") (pinfunction "3_3") (pintype "unspecified"))
      (node (ref "U4") (pin "12") (pinfunction "B1_12") (pintype "unspecified"))
    )
    (net (code "128") (name "Net-(U4-B2)") (class "Default")
      (node (ref "CN4") (pin "4") (pinfunction "4_4") (pintype "unspecified"))
      (node (ref "U4") (pin "11") (pinfunction "B2_11") (pintype "unspecified"))
    )
    (net (code "129") (name "Net-(U4-CLK)") (class "Default")
      (node (ref "J45") (pin "1") (pinfunction "1_1") (pintype "unspecified"))
      (node (ref "U4") (pin "6") (pinfunction "CLK_6") (pintype "unspecified"))
    )
    (net (code "130") (name "Net-(U4-MS1)") (class "Default")
      (node (ref "J42") (pin "2") (pinfunction "2_2") (pintype "input"))
      (node (ref "U4") (pin "2") (pinfunction "MS1_2") (pintype "unspecified"))
    )
    (net (code "131") (name "Net-(U4-MS2)") (class "Default")
      (node (ref "J42") (pin "4") (pinfunction "4_4") (pintype "input"))
      (node (ref "U4") (pin "3") (pinfunction "MS2_3") (pintype "unspecified"))
    )
    (net (code "132") (name "Net-(U5-A1)") (class "Default")
      (node (ref "CN3") (pin "2") (pinfunction "2_2") (pintype "unspecified"))
      (node (ref "U5") (pin "13") (pinfunction "A1_13") (pintype "unspecified"))
    )
    (net (code "133") (name "Net-(U5-A2)") (class "Default")
      (node (ref "CN3") (pin "1") (pinfunction "1_1") (pintype "unspecified"))
      (node (ref "U5") (pin "14") (pinfunction "A2_14") (pintype "unspecified"))
    )
    (net (code "134") (name "Net-(U5-B1)") (class "Default")
      (node (ref "CN3") (pin "3") (pinfunction "3_3") (pintype "unspecified"))
      (node (ref "U5") (pin "12") (pinfunction "B1_12") (pintype "unspecified"))
    )
    (net (code "135") (name "Net-(U5-B2)") (class "Default")
      (node (ref "CN3") (pin "4") (pinfunction "4_4") (pintype "unspecified"))
      (node (ref "U5") (pin "11") (pinfunction "B2_11") (pintype "unspecified"))
    )
    (net (code "136") (name "Net-(U5-CLK)") (class "Default")
      (node (ref "J44") (pin "1") (pinfunction "1_1") (pintype "unspecified"))
      (node (ref "U5") (pin "6") (pinfunction "CLK_6") (pintype "unspecified"))
    )
    (net (code "137") (name "Net-(U5-MS1)") (class "Default")
      (node (ref "J43") (pin "2") (pinfunction "2_2") (pintype "input"))
      (node (ref "U5") (pin "2") (pinfunction "MS1_2") (pintype "unspecified"))
    )
    (net (code "138") (name "Net-(U5-MS2)") (class "Default")
      (node (ref "J43") (pin "4") (pinfunction "4_4") (pintype "input"))
      (node (ref "U5") (pin "3") (pinfunction "MS2_3") (pintype "unspecified"))
    )
    (net (code "139") (name "Net-(U6-VIN)") (class "Default")
      (node (ref "C25") (pin "1") (pinfunction "1_1") (pintype "unspecified"))
      (node (ref "U6") (pin "3") (pinfunction "VIN_3") (pintype "unspecified"))
      (node (ref "USB") (pin "1") (pinfunction "1_1") (pintype "bidirectional"))
    )
    (net (code "140") (name "Net-(U6-VOUT(TAB))") (class "Default")
      (node (ref "C24") (pin "1") (pinfunction "1_1") (pintype "unspecified"))
      (node (ref "C25") (pin "2") (pinfunction "2_2") (pintype "unspecified"))
      (node (ref "R51") (pin "2") (pinfunction "2_2") (pintype "unspecified"))
      (node (ref "U6") (pin "2") (pinfunction "VOUT(TAB)_2") (pintype "unspecified"))
    )
    (net (code "141") (name "Net-(U7-A1)") (class "Default")
      (node (ref "CN7") (pin "2") (pinfunction "2_2") (pintype "unspecified"))
      (node (ref "U7") (pin "13") (pinfunction "A1_13") (pintype "unspecified"))
    )
    (net (code "142") (name "Net-(U7-A2)") (class "Default")
      (node (ref "CN7") (pin "1") (pinfunction "1_1") (pintype "unspecified"))
      (node (ref "U7") (pin "14") (pinfunction "A2_14") (pintype "unspecified"))
    )
    (net (code "143") (name "Net-(U7-B1)") (class "Default")
      (node (ref "CN7") (pin "3") (pinfunction "3_3") (pintype "unspecified"))
      (node (ref "U7") (pin "12") (pinfunction "B1_12") (pintype "unspecified"))
    )
    (net (code "144") (name "Net-(U7-B2)") (class "Default")
      (node (ref "CN7") (pin "4") (pinfunction "4_4") (pintype "unspecified"))
      (node (ref "U7") (pin "11") (pinfunction "B2_11") (pintype "unspecified"))
    )
    (net (code "145") (name "Net-(U7-CLK)") (class "Default")
      (node (ref "J48") (pin "1") (pinfunction "1_1") (pintype "unspecified"))
      (node (ref "U7") (pin "6") (pinfunction "CLK_6") (pintype "unspecified"))
    )
    (net (code "146") (name "Net-(U7-MS1)") (class "Default")
      (node (ref "J36") (pin "2") (pinfunction "2_2") (pintype "input"))
      (node (ref "U7") (pin "2") (pinfunction "MS1_2") (pintype "unspecified"))
    )
    (net (code "147") (name "Net-(U7-MS2)") (class "Default")
      (node (ref "J36") (pin "4") (pinfunction "4_4") (pintype "input"))
      (node (ref "U7") (pin "3") (pinfunction "MS2_3") (pintype "unspecified"))
    )
    (net (code "148") (name "Net-(U8-A1)") (class "Default")
      (node (ref "CN8") (pin "2") (pinfunction "2_2") (pintype "unspecified"))
      (node (ref "U8") (pin "13") (pinfunction "A1_13") (pintype "unspecified"))
    )
    (net (code "149") (name "Net-(U8-A2)") (class "Default")
      (node (ref "CN8") (pin "1") (pinfunction "1_1") (pintype "unspecified"))
      (node (ref "U8") (pin "14") (pinfunction "A2_14") (pintype "unspecified"))
    )
    (net (code "150") (name "Net-(U8-B1)") (class "Default")
      (node (ref "CN8") (pin "3") (pinfunction "3_3") (pintype "unspecified"))
      (node (ref "U8") (pin "12") (pinfunction "B1_12") (pintype "unspecified"))
    )
    (net (code "151") (name "Net-(U8-B2)") (class "Default")
      (node (ref "CN8") (pin "4") (pinfunction "4_4") (pintype "unspecified"))
      (node (ref "U8") (pin "11") (pinfunction "B2_11") (pintype "unspecified"))
    )
    (net (code "152") (name "Net-(U8-CLK)") (class "Default")
      (node (ref "J49") (pin "1") (pinfunction "1_1") (pintype "unspecified"))
      (node (ref "U8") (pin "6") (pinfunction "CLK_6") (pintype "unspecified"))
    )
    (net (code "153") (name "Net-(U8-MS1)") (class "Default")
      (node (ref "J37") (pin "2") (pinfunction "2_2") (pintype "input"))
      (node (ref "U8") (pin "2") (pinfunction "MS1_2") (pintype "unspecified"))
    )
    (net (code "154") (name "Net-(U8-MS2)") (class "Default")
      (node (ref "J37") (pin "4") (pinfunction "4_4") (pintype "input"))
      (node (ref "U8") (pin "3") (pinfunction "MS2_3") (pintype "unspecified"))
    )
    (net (code "155") (name "Net-(U9-A1)") (class "Default")
      (node (ref "CN9") (pin "2") (pinfunction "2_2") (pintype "unspecified"))
      (node (ref "U9") (pin "13") (pinfunction "A1_13") (pintype "unspecified"))
    )
    (net (code "156") (name "Net-(U9-A2)") (class "Default")
      (node (ref "CN9") (pin "1") (pinfunction "1_1") (pintype "unspecified"))
      (node (ref "U9") (pin "14") (pinfunction "A2_14") (pintype "unspecified"))
    )
    (net (code "157") (name "Net-(U9-B1)") (class "Default")
      (node (ref "CN9") (pin "3") (pinfunction "3_3") (pintype "unspecified"))
      (node (ref "U9") (pin "12") (pinfunction "B1_12") (pintype "unspecified"))
    )
    (net (code "158") (name "Net-(U9-B2)") (class "Default")
      (node (ref "CN9") (pin "4") (pinfunction "4_4") (pintype "unspecified"))
      (node (ref "U9") (pin "11") (pinfunction "B2_11") (pintype "unspecified"))
    )
    (net (code "159") (name "Net-(U9-CLK)") (class "Default")
      (node (ref "J50") (pin "1") (pinfunction "1_1") (pintype "unspecified"))
      (node (ref "U9") (pin "6") (pinfunction "CLK_6") (pintype "unspecified"))
    )
    (net (code "160") (name "Net-(U9-MS1)") (class "Default")
      (node (ref "J38") (pin "2") (pinfunction "2_2") (pintype "input"))
      (node (ref "U9") (pin "2") (pinfunction "MS1_2") (pintype "unspecified"))
    )
    (net (code "161") (name "Net-(U9-MS2)") (class "Default")
      (node (ref "J38") (pin "4") (pinfunction "4_4") (pintype "input"))
      (node (ref "U9") (pin "3") (pinfunction "MS2_3") (pintype "unspecified"))
    )
    (net (code "162") (name "Net-(U10-A1)") (class "Default")
      (node (ref "CN10") (pin "2") (pinfunction "2_2") (pintype "unspecified"))
      (node (ref "U10") (pin "13") (pinfunction "A1_13") (pintype "unspecified"))
    )
    (net (code "163") (name "Net-(U10-A2)") (class "Default")
      (node (ref "CN10") (pin "1") (pinfunction "1_1") (pintype "unspecified"))
      (node (ref "U10") (pin "14") (pinfunction "A2_14") (pintype "unspecified"))
    )
    (net (code "164") (name "Net-(U10-B1)") (class "Default")
      (node (ref "CN10") (pin "3") (pinfunction "3_3") (pintype "unspecified"))
      (node (ref "U10") (pin "12") (pinfunction "B1_12") (pintype "unspecified"))
    )
    (net (code "165") (name "Net-(U10-B2)") (class "Default")
      (node (ref "CN10") (pin "4") (pinfunction "4_4") (pintype "unspecified"))
      (node (ref "U10") (pin "11") (pinfunction "B2_11") (pintype "unspecified"))
    )
    (net (code "166") (name "Net-(U10-CLK)") (class "Default")
      (node (ref "J51") (pin "1") (pinfunction "1_1") (pintype "unspecified"))
      (node (ref "U10") (pin "6") (pinfunction "CLK_6") (pintype "unspecified"))
    )
    (net (code "167") (name "Net-(U10-MS1)") (class "Default")
      (node (ref "J39") (pin "2") (pinfunction "2_2") (pintype "input"))
      (node (ref "U10") (pin "2") (pinfunction "MS1_2") (pintype "unspecified"))
    )
    (net (code "168") (name "Net-(U10-MS2)") (class "Default")
      (node (ref "J39") (pin "4") (pinfunction "4_4") (pintype "input"))
      (node (ref "U10") (pin "3") (pinfunction "MS2_3") (pintype "unspecified"))
    )
    (net (code "169") (name "Net-(U15-IN+)") (class "Default")
      (node (ref "U15") (pin "1") (pinfunction "IN+_1") (pintype "unspecified"))
      (node (ref "U16") (pin "1") (pinfunction "1_1") (pintype "unspecified"))
    )
    (net (code "170") (name "Net-(U15-OUT+)") (class "Default")
      (node (ref "FUSE_3_3V") (pin "2") (pinfunction "2_2") (pintype "unspecified"))
      (node (ref "U15") (pin "3") (pinfunction "OUT+_3") (pintype "unspecified"))
    )
    (net (code "171") (name "Net-(U18-OUT1)") (class "Default")
      (node (ref "J20") (pin "2") (pinfunction "2_2") (pintype "unspecified"))
      (node (ref "LED12") (pin "2") (pinfunction "2_2") (pintype "unspecified"))
      (node (ref "U18") (pin "16") (pinfunction "OUT1_16") (pintype "unspecified"))
    )
    (net (code "172") (name "Net-(U18-OUT2)") (class "Default")
      (node (ref "J19") (pin "2") (pinfunction "2_2") (pintype "unspecified"))
      (node (ref "LED11") (pin "2") (pinfunction "2_2") (pintype "unspecified"))
      (node (ref "U18") (pin "15") (pinfunction "OUT2_15") (pintype "unspecified"))
    )
    (net (code "173") (name "Net-(U18-OUT3)") (class "Default")
      (node (ref "J18") (pin "2") (pinfunction "2_2") (pintype "unspecified"))
      (node (ref "LED10") (pin "2") (pinfunction "2_2") (pintype "unspecified"))
      (node (ref "U18") (pin "14") (pinfunction "OUT3_14") (pintype "unspecified"))
    )
    (net (code "174") (name "Net-(U18-OUT4)") (class "Default")
      (node (ref "J16") (pin "2") (pinfunction "2_2") (pintype "unspecified"))
      (node (ref "LED9") (pin "2") (pinfunction "2_2") (pintype "unspecified"))
      (node (ref "U18") (pin "13") (pinfunction "OUT4_13") (pintype "unspecified"))
    )
    (net (code "175") (name "Net-(U19-OUT1)") (class "Default")
      (node (ref "J13") (pin "2") (pinfunction "2_2") (pintype "unspecified"))
      (node (ref "LED13") (pin "2") (pinfunction "2_2") (pintype "unspecified"))
      (node (ref "U19") (pin "16") (pinfunction "OUT1_16") (pintype "unspecified"))
    )
    (net (code "176") (name "Net-(U19-OUT2)") (class "Default")
      (node (ref "J12") (pin "2") (pinfunction "2_2") (pintype "unspecified"))
      (node (ref "LED14") (pin "2") (pinfunction "2_2") (pintype "unspecified"))
      (node (ref "U19") (pin "15") (pinfunction "OUT2_15") (pintype "unspecified"))
    )
    (net (code "177") (name "Net-(U19-OUT3)") (class "Default")
      (node (ref "J11") (pin "2") (pinfunction "2_2") (pintype "unspecified"))
      (node (ref "LED15") (pin "2") (pinfunction "2_2") (pintype "unspecified"))
      (node (ref "U19") (pin "14") (pinfunction "OUT3_14") (pintype "unspecified"))
    )
    (net (code "178") (name "Net-(U19-OUT4)") (class "Default")
      (node (ref "J9") (pin "2") (pinfunction "2_2") (pintype "unspecified"))
      (node (ref "LED16") (pin "2") (pinfunction "2_2") (pintype "unspecified"))
      (node (ref "U19") (pin "13") (pinfunction "OUT4_13") (pintype "unspecified"))
    )
    (net (code "179") (name "Net-(USB_SER-CTS)") (class "Default")
      (node (ref "J53") (pin "1") (pinfunction "1_1") (pintype "unspecified"))
      (node (ref "USB_SER") (pin "13") (pinfunction "CTS_13") (pintype "unspecified"))
    )
    (net (code "180") (name "Net-(USB_SER-D+)") (class "Default")
      (node (ref "USB") (pin "3") (pinfunction "3_3") (pintype "bidirectional"))
      (node (ref "USB_SER") (pin "19") (pinfunction "D+_19") (pintype "unspecified"))
    )
    (net (code "181") (name "Net-(USB_SER-D-)") (class "Default")
      (node (ref "USB") (pin "2") (pinfunction "2_2") (pintype "bidirectional"))
      (node (ref "USB_SER") (pin "18") (pinfunction "D-_18") (pintype "unspecified"))
    )
    (net (code "182") (name "Net-(USB_SER-GP6{slash}RXLED)") (class "Default")
      (node (ref "R45") (pin "2") (pinfunction "2_2") (pintype "unspecified"))
      (node (ref "USB_SER") (pin "6") (pinfunction "GP6/RXLED_6") (pintype "unspecified"))
    )
    (net (code "183") (name "Net-(USB_SER-GP7{slash}TXLED)") (class "Default")
      (node (ref "R27") (pin "2") (pinfunction "2_2") (pintype "unspecified"))
      (node (ref "USB_SER") (pin "5") (pinfunction "GP7/TXLED_5") (pintype "unspecified"))
    )
    (net (code "184") (name "Net-(USB_SER-OSC1)") (class "Default")
      (node (ref "C22") (pin "2") (pinfunction "2_2") (pintype "unspecified"))
      (node (ref "USB_SER") (pin "2") (pinfunction "OSC1_2") (pintype "unspecified"))
      (node (ref "X2") (pin "1") (pinfunction "OSC1_1") (pintype "input"))
    )
    (net (code "185") (name "Net-(USB_SER-OSC2)") (class "Default")
      (node (ref "C21") (pin "2") (pinfunction "2_2") (pintype "unspecified"))
      (node (ref "USB_SER") (pin "3") (pinfunction "OSC2_3") (pintype "unspecified"))
      (node (ref "X2") (pin "2") (pinfunction "OSC2_2") (pintype "input"))
    )
    (net (code "186") (name "Net-(USB_SER-RST)") (class "Default")
      (node (ref "R46") (pin "2") (pinfunction "2_2") (pintype "unspecified"))
      (node (ref "R50") (pin "2") (pinfunction "2_2") (pintype "unspecified"))
      (node (ref "R51") (pin "1") (pinfunction "1_1") (pintype "unspecified"))
      (node (ref "USB_SER") (pin "4") (pinfunction "RST_4") (pintype "unspecified"))
    )
    (net (code "187") (name "Net-(USB_SER-RTS)") (class "Default")
      (node (ref "J53") (pin "2") (pinfunction "2_2") (pintype "unspecified"))
      (node (ref "USB_SER") (pin "11") (pinfunction "RTS_11") (pintype "unspecified"))
    )
    (net (code "188") (name "Net-(USB_SER-RX)") (class "Default")
      (node (ref "J52") (pin "2") (pinfunction "2_2") (pintype "unspecified"))
      (node (ref "USB_SER") (pin "12") (pinfunction "RX_12") (pintype "unspecified"))
    )
    (net (code "189") (name "Net-(USB_SER-TX)") (class "Default")
      (node (ref "J52") (pin "1") (pinfunction "1_1") (pintype "unspecified"))
      (node (ref "USB_SER") (pin "10") (pinfunction "TX_10") (pintype "unspecified"))
    )
    (net (code "190") (name "Net-(USB_SER-VDD)") (class "Default")
      (node (ref "R46") (pin "1") (pinfunction "1_1") (pintype "unspecified"))
      (node (ref "USB_SER") (pin "1") (pinfunction "VDD_1") (pintype "unspecified"))
    )
    (net (code "191") (name "Net-(USB_SER-VUSB)") (class "Default")
      (node (ref "C23") (pin "1") (pinfunction "1_1") (pintype "unspecified"))
      (node (ref "USB_SER") (pin "17") (pinfunction "VUSB_17") (pintype "unspecified"))
    )
    (net (code "192") (name "PRINT FAN 1") (class "Default")
      (node (ref "BRAIN") (pin "99") (pinfunction "DAC_EXTI9/DCMI_D3/I2C3_SDA/I2S_CKIN/QUADSPI_BK1_IO0/RCC_MCO_2/SDMMC1_D1/TIM3_CH4/TIM8_CH4/UART5_CTS/PC9_99") (pintype "bidirectional"))
      (node (ref "U18") (pin "1") (pinfunction "IN1_1") (pintype "unspecified"))
    )
    (net (code "193") (name "PRINT FAN 2") (class "Default")
      (node (ref "BRAIN") (pin "98") (pinfunction "DCMI_D2/SDMMC1_D0/SYS_TRACED1/TIM3_CH3/TIM8_CH3/UART5_RTS/USART6_CK/PC8_98") (pintype "bidirectional"))
      (node (ref "U18") (pin "2") (pinfunction "IN2_2") (pintype "unspecified"))
    )
    (net (code "194") (name "PRINT FAN 3") (class "Default")
      (node (ref "BRAIN") (pin "97") (pinfunction "DCMI_D1/I2S3_MCK/LTDC_G6/SDMMC1_D7/TIM3_CH2/TIM8_CH2/USART6_RX/PC7_97") (pintype "bidirectional"))
      (node (ref "U18") (pin "3") (pinfunction "IN3_3") (pintype "unspecified"))
    )
    (net (code "195") (name "PRINT FAN 4") (class "Default")
      (node (ref "BRAIN") (pin "96") (pinfunction "DCMI_D0/I2S2_MCK/LTDC_HSYNC/SDMMC1_D6/TIM3_CH1/TIM8_CH1/USART6_TX/PC6_96") (pintype "bidirectional"))
      (node (ref "U18") (pin "4") (pinfunction "IN4_4") (pintype "unspecified"))
    )
    (net (code "196") (name "PROBE") (class "Default")
      (node (ref "BRAIN") (pin "1") (pinfunction "PE2/ETH_TXD3/FMC_A23/QUADSPI_BK1_IO2/SAI1_MCLK_A/SPI4_SCK/SYS_TRACECLK_1") (pintype "bidirectional"))
      (node (ref "PROBE") (pin "1") (pinfunction "1_1") (pintype "input"))
    )
    (net (code "197") (name "PWR") (class "Default")
      (node (ref "FUSE_HEAT") (pin "1") (pinfunction "1_1") (pintype "unspecified"))
      (node (ref "P12") (pin "1") (pinfunction "1_1") (pintype "unspecified"))
      (node (ref "P13") (pin "1") (pinfunction "1_1") (pintype "unspecified"))
      (node (ref "P14") (pin "1") (pinfunction "1_1") (pintype "unspecified"))
      (node (ref "P15") (pin "1") (pinfunction "1_1") (pintype "unspecified"))
      (node (ref "R18") (pin "2") (pinfunction "2_2") (pintype "unspecified"))
      (node (ref "R19") (pin "2") (pinfunction "2_2") (pintype "unspecified"))
      (node (ref "R21") (pin "2") (pinfunction "2_2") (pintype "unspecified"))
      (node (ref "R23") (pin "2") (pinfunction "2_2") (pintype "unspecified"))
    )
    (net (code "198") (name "RESET") (class "Default")
      (node (ref "BRAIN") (pin "25") (pinfunction "NRST_25") (pintype "input"))
      (node (ref "EXP2") (pin "8") (pinfunction "8_8") (pintype "unspecified"))
      (node (ref "J8") (pin "5") (pinfunction "5_5") (pintype "input"))
      (node (ref "R28") (pin "1") (pinfunction "1_1") (pintype "unspecified"))
      (node (ref "RESET") (pin "3") (pinfunction "3_3") (pintype "unspecified"))
      (node (ref "RESET") (pin "4") (pinfunction "4_4") (pintype "unspecified"))
    )
    (net (code "199") (name "RS") (class "Default")
      (node (ref "BRAIN") (pin "113") (pinfunction "DCMI_D9/I2S3_SD/SDMMC1_CK/SPI3_MOSI/SYS_TRACED3/UART5_TX/USART3_CK/PC12_113") (pintype "bidirectional"))
      (node (ref "EXP1") (pin "7") (pinfunction "7_7") (pintype "unspecified"))
    )
    (net (code "200") (name "SCK") (class "Default")
      (node (ref "EXP2") (pin "2") (pinfunction "2_2") (pintype "unspecified"))
      (node (ref "R32") (pin "2") (pinfunction "2_2") (pintype "unspecified"))
      (node (ref "SCK_EN") (pin "1") (pinfunction "1_1") (pintype "unspecified"))
      (node (ref "SDCARD") (pin "5") (pinfunction "CLK_5") (pintype "input"))
    )
    (net (code "201") (name "SD_PRES") (class "Default")
      (node (ref "BRAIN") (pin "74") (pinfunction "CAN2_TX/ETH_TXD1/I2S2_CK/SPI2_SCK/TIM1_CH1N/USART3_CTS/USB_OTG_HS_ULPI_D6/USB_OTG_HS_VBUS/PB13_74") (pintype "bidirectional"))
      (node (ref "EXP2") (pin "7") (pinfunction "7_7") (pintype "unspecified"))
      (node (ref "R61") (pin "1") (pinfunction "1_1") (pintype "unspecified"))
    )
    (net (code "202") (name "SD_PRES1") (class "Default")
      (node (ref "BRAIN") (pin "104") (pinfunction "CAN1_TX/LTDC_R5/SAI2_FS_B/TIM1_ETR/USART1_RTS/USB_OTG_FS_DP/PA12_104") (pintype "bidirectional"))
      (node (ref "R35") (pin "1") (pinfunction "1_1") (pintype "unspecified"))
      (node (ref "R58") (pin "1") (pinfunction "1_1") (pintype "unspecified"))
    )
    (net (code "203") (name "SD_SS") (class "Default")
      (node (ref "BRAIN") (pin "73") (pinfunction "CAN2_RX/ETH_TXD0/I2C2_SMBA/I2S2_WS/SPI2_NSS/TIM1_BKIN/USART3_CK/USB_OTG_HS_ID/USB_OTG_HS_ULPI_D5/PB12_73") (pintype "bidirectional"))
      (node (ref "EXP2") (pin "4") (pinfunction "4_4") (pintype "unspecified"))
      (node (ref "R60") (pin "1") (pinfunction "1_1") (pintype "unspecified"))
    )
    (net (code "204") (name "SD_SS1") (class "Default")
      (node (ref "BRAIN") (pin "103") (pinfunction "ADC1_EXTI11/ADC2_EXTI11/ADC3_EXTI11/CAN1_RX/LTDC_R4/TIM1_CH4/USART1_CTS/USB_OTG_FS_DM/PA11_103") (pintype "bidirectional"))
      (node (ref "R33") (pin "1") (pinfunction "1_1") (pintype "unspecified"))
      (node (ref "R56") (pin "2") (pinfunction "2_2") (pintype "unspecified"))
    )
    (net (code "205") (name "SERVO") (class "Default")
      (node (ref "BLTOUCH") (pin "3") (pinfunction "3_3") (pintype "input"))
      (node (ref "BRAIN") (pin "21") (pinfunction "PF9/ADC3_IN7/DAC_EXTI9/QUADSPI_BK1_IO1/SAI1_FS_B/SPI5_MOSI/TIM14_CH1/UART7_CTS_21") (pintype "bidirectional"))
    )
    (net (code "206") (name "SERVO1") (class "Default")
      (node (ref "BRAIN") (pin "82") (pinfunction "FMC_A18/I2C4_SDA/LPTIM1_OUT/QUADSPI_BK1_IO3/SAI2_SCK_A/TIM4_CH2/PD13_82") (pintype "bidirectional"))
      (node (ref "SERVO1") (pin "2") (pinfunction "2_2") (pintype "input"))
    )
    (net (code "207") (name "SERVO2") (class "Default")
      (node (ref "BRAIN") (pin "81") (pinfunction "FMC_A17/FMC_ALE/I2C4_SCL/LPTIM1_IN1/QUADSPI_BK1_IO1/SAI2_FS_A/TIM4_CH1/USART3_RTS/PD12_81") (pintype "bidirectional"))
      (node (ref "SERVO2") (pin "2") (pinfunction "2_2") (pintype "input"))
    )
    (net (code "208") (name "SWCLK") (class "Default")
      (node (ref "BRAIN") (pin "109") (pinfunction "SYS_JTCK-SWCLK/PA14_109") (pintype "bidirectional"))
      (node (ref "J8") (pin "3") (pinfunction "3_3") (pintype "input"))
    )
    (net (code "209") (name "SWIDO") (class "Default")
      (node (ref "BRAIN") (pin "105") (pinfunction "SYS_JTMS-SWDIO/PA13_105") (pintype "bidirectional"))
      (node (ref "J55") (pin "2") (pinfunction "2_2") (pintype "unspecified"))
      (node (ref "J8") (pin "4") (pinfunction "4_4") (pintype "input"))
    )
    (net (code "210") (name "SWO") (class "Default")
      (node (ref "BRAIN") (pin "133") (pinfunction "I2S1_CK/I2S3_CK/SPI1_SCK/SPI3_SCK/SYS_JTDO-SWO/TIM2_CH2/PB3_133") (pintype "bidirectional"))
      (node (ref "J8") (pin "6") (pinfunction "6_6") (pintype "input"))
      (node (ref "SCK_EN") (pin "2") (pinfunction "2_2") (pintype "unspecified"))
    )
    (net (code "211") (name "TBED1") (class "Default")
      (node (ref "BRAIN") (pin "41") (pinfunction "ADC1_IN5/ADC2_IN5/DAC_OUT2/I2S1_CK/LTDC_R4/SPI1_SCK/TIM2_CH1/TIM2_ETR/TIM8_CH1N/USB_OTG_HS_ULPI_CK/PA5_41") (pintype "bidirectional"))
      (node (ref "C7") (pin "2") (pinfunction "2_2") (pintype "unspecified"))
      (node (ref "J1") (pin "9") (pinfunction "9_9") (pintype "unspecified"))
      (node (ref "R7") (pin "1") (pinfunction "1_1") (pintype "unspecified"))
    )
    (net (code "212") (name "TEMP1") (class "Default")
      (node (ref "BRAIN") (pin "47") (pinfunction "ADC1_IN9/ADC2_IN9/ETH_RXD3/LTDC_R6/TIM1_CH3N/TIM3_CH4/TIM8_CH3N/USB_OTG_HS_ULPI_D2/PB1_47") (pintype "bidirectional"))
      (node (ref "C1") (pin "2") (pinfunction "2_2") (pintype "unspecified"))
      (node (ref "J1") (pin "1") (pinfunction "1_1") (pintype "unspecified"))
      (node (ref "R1") (pin "1") (pinfunction "1_1") (pintype "unspecified"))
    )
    (net (code "213") (name "TEMP2") (class "Default")
      (node (ref "BRAIN") (pin "46") (pinfunction "ADC1_IN8/ADC2_IN8/ETH_RXD2/LTDC_R3/TIM1_CH2N/TIM3_CH3/TIM8_CH2N/UART4_CTS/USB_OTG_HS_ULPI_D1/PB0_46") (pintype "bidirectional"))
      (node (ref "C2") (pin "2") (pinfunction "2_2") (pintype "unspecified"))
      (node (ref "J1") (pin "3") (pinfunction "3_3") (pintype "unspecified"))
      (node (ref "R2") (pin "1") (pinfunction "1_1") (pintype "unspecified"))
    )
    (net (code "214") (name "TEMP3") (class "Default")
      (node (ref "BRAIN") (pin "43") (pinfunction "ADC1_IN7/ADC2_IN7/ETH_CRS_DV/ETH_RX_DV/FMC_SDNWE/I2S1_SD/SPI1_MOSI/TIM14_CH1/TIM1_CH1N/TIM3_CH2/TIM8_CH1N/PA7_43") (pintype "bidirectional"))
      (node (ref "C3") (pin "2") (pinfunction "2_2") (pintype "unspecified"))
      (node (ref "J1") (pin "5") (pinfunction "5_5") (pintype "unspecified"))
      (node (ref "R3") (pin "1") (pinfunction "1_1") (pintype "unspecified"))
    )
    (net (code "215") (name "TEMP4") (class "Default")
      (node (ref "BRAIN") (pin "42") (pinfunction "ADC1_IN6/ADC2_IN6/DCMI_PIXCLK/LTDC_G2/SPI1_MISO/TIM13_CH1/TIM1_BKIN/TIM3_CH1/TIM8_BKIN/PA6_42") (pintype "bidirectional"))
      (node (ref "C4") (pin "2") (pinfunction "2_2") (pintype "unspecified"))
      (node (ref "J1") (pin "7") (pinfunction "7_7") (pintype "unspecified"))
      (node (ref "R4") (pin "1") (pinfunction "1_1") (pintype "unspecified"))
    )
    (net (code "216") (name "UART1RX") (class "Default")
      (node (ref "BRAIN") (pin "102") (pinfunction "DCMI_D1/TIM1_CH3/USART1_RX/USB_OTG_FS_ID/PA10_102") (pintype "bidirectional"))
      (node (ref "UART1") (pin "1") (pinfunction "1_1") (pintype "unspecified"))
    )
    (net (code "217") (name "UART1TX") (class "Default")
      (node (ref "BRAIN") (pin "101") (pinfunction "DAC_EXTI9/DCMI_D0/I2C3_SMBA/I2S2_CK/SPI2_SCK/TIM1_CH2/USART1_TX/USB_OTG_FS_VBUS/PA9_101") (pintype "bidirectional"))
      (node (ref "UART1") (pin "2") (pinfunction "2_2") (pintype "unspecified"))
    )
    (net (code "218") (name "UART2RX") (class "Default")
      (node (ref "BRAIN") (pin "37") (pinfunction "ADC1_IN3/ADC2_IN3/ADC3_IN3/ETH_COL/LTDC_B5/TIM2_CH4/TIM5_CH4/TIM9_CH2/USART2_RX/USB_OTG_HS_ULPI_D0/PA3_37") (pintype "bidirectional"))
      (node (ref "UART2") (pin "1") (pinfunction "1_1") (pintype "unspecified"))
    )
    (net (code "219") (name "UART2TX") (class "Default")
      (node (ref "BRAIN") (pin "36") (pinfunction "ADC1_IN2/ADC2_IN2/ADC3_IN2/ETH_MDIO/LTDC_R1/SAI2_SCK_B/SYS_WKUP1/TIM2_CH3/TIM5_CH3/TIM9_CH1/USART2_TX/PA2_36") (pintype "bidirectional"))
      (node (ref "UART2") (pin "2") (pinfunction "2_2") (pintype "unspecified"))
    )
    (net (code "220") (name "UARTNextionRX") (class "Default")
      (node (ref "BRAIN") (pin "35") (pinfunction "ADC1_IN1/ADC2_IN1/ADC3_IN1/ETH_REF_CLK/ETH_RX_CLK/LTDC_R2/QUADSPI_BK1_IO3/SAI2_MCLK_B/TIM2_CH2/TIM5_CH2/UART4_RX/USART2_RTS/PA1_35") (pintype "bidirectional"))
      (node (ref "NEXTION") (pin "2") (pinfunction "2_2") (pintype "unspecified"))
    )
    (net (code "221") (name "UARTNextionTX") (class "Default")
      (node (ref "BRAIN") (pin "34") (pinfunction "ADC1_IN0/ADC2_IN0/ADC3_IN0/ETH_CRS/SAI2_SD_B/SYS_WKUP0/TIM2_CH1/TIM2_ETR/TIM5_CH1/TIM8_ETR/UART4_TX/USART2_CTS/PA0_34") (pintype "bidirectional"))
      (node (ref "NEXTION") (pin "3") (pinfunction "3_3") (pintype "unspecified"))
    )
    (net (code "222") (name "VCC") (class "Default")
      (node (ref "BLTOUCH") (pin "2") (pinfunction "2_2") (pintype "input"))
      (node (ref "BOOTSEL") (pin "1") (pinfunction "1_1") (pintype "unspecified"))
      (node (ref "BRAIN") (pin "108") (pinfunction "VDD_108") (pintype "bidirectional"))
      (node (ref "BRAIN") (pin "121") (pinfunction "VDD_121") (pintype "bidirectional"))
      (node (ref "BRAIN") (pin "131") (pinfunction "VDD_131") (pintype "bidirectional"))
      (node (ref "BRAIN") (pin "144") (pinfunction "VDD_144") (pintype "bidirectional"))
      (node (ref "BRAIN") (pin "17") (pinfunction "VDD_17") (pintype "bidirectional"))
      (node (ref "BRAIN") (pin "30") (pinfunction "VDD_30") (pintype "bidirectional"))
      (node (ref "BRAIN") (pin "32") (pinfunction "VREF+_32") (pintype "bidirectional"))
      (node (ref "BRAIN") (pin "33") (pinfunction "VDDA_33") (pintype "bidirectional"))
      (node (ref "BRAIN") (pin "39") (pinfunction "VDD_39") (pintype "bidirectional"))
      (node (ref "BRAIN") (pin "52") (pinfunction "VDD_52") (pintype "bidirectional"))
      (node (ref "BRAIN") (pin "62") (pinfunction "VDD_62") (pintype "bidirectional"))
      (node (ref "BRAIN") (pin "72") (pinfunction "VDD_72") (pintype "bidirectional"))
      (node (ref "BRAIN") (pin "84") (pinfunction "VDD_84") (pintype "bidirectional"))
      (node (ref "BRAIN") (pin "95") (pinfunction "VDDUSB_95") (pintype "bidirectional"))
      (node (ref "C10") (pin "2") (pinfunction "2_2") (pintype "unspecified"))
      (node (ref "C11") (pin "2") (pinfunction "2_2") (pintype "unspecified"))
      (node (ref "C12") (pin "2") (pinfunction "2_2") (pintype "unspecified"))
      (node (ref "C13") (pin "2") (pinfunction "2_2") (pintype "unspecified"))
      (node (ref "C14") (pin "2") (pinfunction "2_2") (pintype "unspecified"))
      (node (ref "C15") (pin "2") (pinfunction "2_2") (pintype "unspecified"))
      (node (ref "C16") (pin "2") (pinfunction "2_2") (pintype "unspecified"))
      (node (ref "C5") (pin "2") (pinfunction "2_2") (pintype "unspecified"))
      (node (ref "C6") (pin "2") (pinfunction "2_2") (pintype "unspecified"))
      (node (ref "C8") (pin "2") (pinfunction "2_2") (pintype "unspecified"))
      (node (ref "EXP1") (pin "1") (pinfunction "1_1") (pintype "unspecified"))
      (node (ref "FEND1") (pin "1") (pinfunction "1_1") (pintype "input"))
      (node (ref "FEND2") (pin "1") (pinfunction "1_1") (pintype "input"))
      (node (ref "FEND3") (pin "1") (pinfunction "1_1") (pintype "input"))
      (node (ref "FEND4") (pin "1") (pinfunction "1_1") (pintype "input"))
      (node (ref "FUSE_3_3V") (pin "1") (pinfunction "1_1") (pintype "unspecified"))
      (node (ref "I2C1") (pin "3") (pinfunction "3_3") (pintype "unspecified"))
      (node (ref "I2C2") (pin "3") (pinfunction "3_3") (pintype "unspecified"))
      (node (ref "I2C3") (pin "3") (pinfunction "3_3") (pintype "unspecified"))
      (node (ref "I2C4") (pin "3") (pinfunction "3_3") (pintype "unspecified"))
      (node (ref "I2C5") (pin "3") (pinfunction "3_3") (pintype "unspecified"))
      (node (ref "J36") (pin "1") (pinfunction "1_1") (pintype "input"))
      (node (ref "J36") (pin "3") (pinfunction "3_3") (pintype "input"))
      (node (ref "J36") (pin "5") (pinfunction "5_5") (pintype "input"))
      (node (ref "J37") (pin "1") (pinfunction "1_1") (pintype "input"))
      (node (ref "J37") (pin "3") (pinfunction "3_3") (pintype "input"))
      (node (ref "J37") (pin "5") (pinfunction "5_5") (pintype "input"))
      (node (ref "J38") (pin "1") (pinfunction "1_1") (pintype "input"))
      (node (ref "J38") (pin "3") (pinfunction "3_3") (pintype "input"))
      (node (ref "J38") (pin "5") (pinfunction "5_5") (pintype "input"))
      (node (ref "J39") (pin "1") (pinfunction "1_1") (pintype "input"))
      (node (ref "J39") (pin "3") (pinfunction "3_3") (pintype "input"))
      (node (ref "J39") (pin "5") (pinfunction "5_5") (pintype "input"))
      (node (ref "J40") (pin "1") (pinfunction "1_1") (pintype "input"))
      (node (ref "J40") (pin "3") (pinfunction "3_3") (pintype "input"))
      (node (ref "J40") (pin "5") (pinfunction "5_5") (pintype "input"))
      (node (ref "J41") (pin "1") (pinfunction "1_1") (pintype "input"))
      (node (ref "J41") (pin "3") (pinfunction "3_3") (pintype "input"))
      (node (ref "J41") (pin "5") (pinfunction "5_5") (pintype "input"))
      (node (ref "J42") (pin "1") (pinfunction "1_1") (pintype "input"))
      (node (ref "J42") (pin "3") (pinfunction "3_3") (pintype "input"))
      (node (ref "J42") (pin "5") (pinfunction "5_5") (pintype "input"))
      (node (ref "J43") (pin "1") (pinfunction "1_1") (pintype "input"))
      (node (ref "J43") (pin "3") (pinfunction "3_3") (pintype "input"))
      (node (ref "J43") (pin "5") (pinfunction "5_5") (pintype "input"))
      (node (ref "J8") (pin "2") (pinfunction "2_2") (pintype "input"))
      (node (ref "NEXTION") (pin "1") (pinfunction "1_1") (pintype "unspecified"))
      (node (ref "R1") (pin "2") (pinfunction "2_2") (pintype "unspecified"))
      (node (ref "R10") (pin "1") (pinfunction "1_1") (pintype "unspecified"))
      (node (ref "R15") (pin "1") (pinfunction "1_1") (pintype "unspecified"))
      (node (ref "R16") (pin "1") (pinfunction "1_1") (pintype "unspecified"))
      (node (ref "R2") (pin "2") (pinfunction "2_2") (pintype "unspecified"))
      (node (ref "R25") (pin "1") (pinfunction "1_1") (pintype "unspecified"))
      (node (ref "R26") (pin "1") (pinfunction "1_1") (pintype "unspecified"))
      (node (ref "R28") (pin "2") (pinfunction "2_2") (pintype "unspecified"))
      (node (ref "R29") (pin "2") (pinfunction "2_2") (pintype "unspecified"))
      (node (ref "R3") (pin "2") (pinfunction "2_2") (pintype "unspecified"))
      (node (ref "R30") (pin "2") (pinfunction "2_2") (pintype "unspecified"))
      (node (ref "R31") (pin "2") (pinfunction "2_2") (pintype "unspecified"))
      (node (ref "R4") (pin "2") (pinfunction "2_2") (pintype "unspecified"))
      (node (ref "R48") (pin "1") (pinfunction "1_1") (pintype "unspecified"))
      (node (ref "R5") (pin "1") (pinfunction "1_1") (pintype "unspecified"))
      (node (ref "R50") (pin "1") (pinfunction "1_1") (pintype "unspecified"))
      (node (ref "R52") (pin "2") (pinfunction "2_2") (pintype "unspecified"))
      (node (ref "R53") (pin "2") (pinfunction "2_2") (pintype "unspecified"))
      (node (ref "R6") (pin "1") (pinfunction "1_1") (pintype "unspecified"))
      (node (ref "R7") (pin "2") (pinfunction "2_2") (pintype "unspecified"))
      (node (ref "R8") (pin "1") (pinfunction "1_1") (pintype "unspecified"))
      (node (ref "R9") (pin "2") (pinfunction "2_2") (pintype "unspecified"))
      (node (ref "SDCARD") (pin "4") (pinfunction "VDD_4") (pintype "bidirectional"))
      (node (ref "U10") (pin "10") (pinfunction "VIO_10") (pintype "unspecified"))
      (node (ref "U2") (pin "10") (pinfunction "VIO_10") (pintype "unspecified"))
      (node (ref "U3") (pin "10") (pinfunction "VIO_10") (pintype "unspecified"))
      (node (ref "U4") (pin "10") (pinfunction "VIO_10") (pintype "unspecified"))
      (node (ref "U5") (pin "10") (pinfunction "VIO_10") (pintype "unspecified"))
      (node (ref "U7") (pin "10") (pinfunction "VIO_10") (pintype "unspecified"))
      (node (ref "U8") (pin "10") (pinfunction "VIO_10") (pintype "unspecified"))
      (node (ref "U9") (pin "10") (pinfunction "VIO_10") (pintype "unspecified"))
      (node (ref "XMAX") (pin "1") (pinfunction "1_1") (pintype "input"))
      (node (ref "XMIN") (pin "1") (pinfunction "1_1") (pintype "input"))
      (node (ref "YMAX") (pin "1") (pinfunction "1_1") (pintype "input"))
      (node (ref "YMIN") (pin "1") (pinfunction "1_1") (pintype "input"))
      (node (ref "Z1MAX") (pin "1") (pinfunction "1_1") (pintype "input"))
      (node (ref "Z1MIN") (pin "1") (pinfunction "1_1") (pintype "input"))
      (node (ref "Z2MAX") (pin "1") (pinfunction "1_1") (pintype "input"))
      (node (ref "Z2MIN") (pin "1") (pinfunction "1_1") (pintype "input"))
    )
    (net (code "223") (name "XDIR") (class "Default")
      (node (ref "BRAIN") (pin "26") (pinfunction "ADC1_IN10/ADC2_IN10/ADC3_IN10/FMC_SDNWE/LTDC_R5/SAI2_FS_B/USB_OTG_HS_ULPI_STP/PC0_26") (pintype "bidirectional"))
      (node (ref "U2") (pin "8") (pinfunction "DIR_8") (pintype "unspecified"))
    )
    (net (code "224") (name "XEN") (class "Default")
      (node (ref "BRAIN") (pin "44") (pinfunction "ADC1_IN14/ADC2_IN14/ETH_RXD0/FMC_SDNE0/I2S1_MCK/SPDIFRX_IN2/PC4_44") (pintype "bidirectional"))
      (node (ref "R15") (pin "2") (pinfunction "2_2") (pintype "unspecified"))
      (node (ref "U2") (pin "1") (pinfunction "EN_1") (pintype "unspecified"))
    )
    (net (code "225") (name "XMAX") (class "Default")
      (node (ref "BRAIN") (pin "49") (pinfunction "PF11/ADC1_EXTI11/ADC2_EXTI11/ADC3_EXTI11/DCMI_D12/FMC_SDNRAS/SAI2_SD_B/SPI5_MOSI_49") (pintype "bidirectional"))
      (node (ref "XMAX") (pin "3") (pinfunction "3_3") (pintype "input"))
    )
    (net (code "226") (name "XMIN") (class "Default")
      (node (ref "BRAIN") (pin "48") (pinfunction "I2S3_SD/QUADSPI_CLK/SAI1_SD_A/SPI3_MOSI/PB2_48") (pintype "bidirectional"))
      (node (ref "XMIN") (pin "3") (pinfunction "3_3") (pintype "input"))
    )
    (net (code "227") (name "XRX") (class "Default")
      (node (ref "BRAIN") (pin "28") (pinfunction "ADC1_IN12/ADC2_IN12/ADC3_IN12/ETH_TXD2/FMC_SDNE0/SPI2_MISO/USB_OTG_HS_ULPI_DIR/PC2_28") (pintype "bidirectional"))
      (node (ref "J47") (pin "2") (pinfunction "2_2") (pintype "unspecified"))
      (node (ref "U2") (pin "5") (pinfunction "RX_5") (pintype "unspecified"))
    )
    (net (code "228") (name "XSTEP") (class "Default")
      (node (ref "BRAIN") (pin "27") (pinfunction "ADC1_IN11/ADC2_IN11/ADC3_IN11/ETH_MDC/I2S2_SD/RTC_TAMP3/RTC_TS/SAI1_SD_A/SPI2_MOSI/SYS_TRACED0/SYS_WKUP5/PC1_27") (pintype "bidirectional"))
      (node (ref "U2") (pin "7") (pinfunction "STEP_7") (pintype "unspecified"))
    )
    (net (code "229") (name "XTX") (class "Default")
      (node (ref "BRAIN") (pin "29") (pinfunction "ADC1_IN13/ADC2_IN13/ADC3_IN13/ETH_TX_CLK/FMC_SDCKE0/I2S2_SD/SPI2_MOSI/USB_OTG_HS_ULPI_NXT/PC3_29") (pintype "bidirectional"))
      (node (ref "J40") (pin "6") (pinfunction "6_6") (pintype "input"))
      (node (ref "U2") (pin "4") (pinfunction "TX_4") (pintype "unspecified"))
    )
    (net (code "230") (name "YDIR") (class "Default")
      (node (ref "BRAIN") (pin "18") (pinfunction "PF6/ADC3_IN4/QUADSPI_BK1_IO3/SAI1_SD_B/SPI5_NSS/TIM10_CH1/UART7_RX_18") (pintype "bidirectional"))
      (node (ref "U3") (pin "8") (pinfunction "DIR_8") (pintype "unspecified"))
    )
    (net (code "231") (name "YEN") (class "Default")
      (node (ref "BRAIN") (pin "68") (pinfunction "PE15/FMC_D12/FMC_DA12/LTDC_R7/TIM1_BKIN_68") (pintype "bidirectional"))
      (node (ref "R16") (pin "2") (pinfunction "2_2") (pintype "unspecified"))
      (node (ref "U3") (pin "1") (pinfunction "EN_1") (pintype "unspecified"))
    )
    (net (code "232") (name "YMAX") (class "Default")
      (node (ref "BRAIN") (pin "53") (pinfunction "PF13/FMC_A7/I2C4_SMBA_53") (pintype "bidirectional"))
      (node (ref "YMAX") (pin "3") (pinfunction "3_3") (pintype "input"))
    )
    (net (code "233") (name "YMIN") (class "Default")
      (node (ref "BRAIN") (pin "50") (pinfunction "PF12/FMC_A6_50") (pintype "bidirectional"))
      (node (ref "YMIN") (pin "3") (pinfunction "3_3") (pintype "input"))
    )
    (net (code "234") (name "YRX") (class "Default")
      (node (ref "BRAIN") (pin "19") (pinfunction "PF7/ADC3_IN5/QUADSPI_BK1_IO2/SAI1_MCLK_B/SPI5_SCK/TIM11_CH1/UART7_TX_19") (pintype "bidirectional"))
      (node (ref "J46") (pin "2") (pinfunction "2_2") (pintype "unspecified"))
      (node (ref "U3") (pin "5") (pinfunction "RX_5") (pintype "unspecified"))
    )
    (net (code "235") (name "YSTEP") (class "Default")
      (node (ref "BRAIN") (pin "15") (pinfunction "PF5/ADC3_IN15/FMC_A5_15") (pintype "bidirectional"))
      (node (ref "U3") (pin "7") (pinfunction "STEP_7") (pintype "unspecified"))
    )
    (net (code "236") (name "YTX") (class "Default")
      (node (ref "BRAIN") (pin "20") (pinfunction "PF8/ADC3_IN6/QUADSPI_BK1_IO0/SAI1_SCK_B/SPI5_MISO/TIM13_CH1/UART7_RTS_20") (pintype "bidirectional"))
      (node (ref "J41") (pin "6") (pinfunction "6_6") (pintype "input"))
      (node (ref "U3") (pin "4") (pinfunction "TX_4") (pintype "unspecified"))
    )
    (net (code "237") (name "Z1RX") (class "Default")
      (node (ref "BRAIN") (pin "11") (pinfunction "PF1/FMC_A1/I2C2_SCL_11") (pintype "bidirectional"))
      (node (ref "J45") (pin "2") (pinfunction "2_2") (pintype "unspecified"))
      (node (ref "U4") (pin "5") (pinfunction "RX_5") (pintype "unspecified"))
    )
    (net (code "238") (name "Z1TX") (class "Default")
      (node (ref "BRAIN") (pin "12") (pinfunction "PF2/FMC_A2/I2C2_SMBA_12") (pintype "bidirectional"))
      (node (ref "J42") (pin "6") (pinfunction "6_6") (pintype "input"))
      (node (ref "U4") (pin "4") (pinfunction "TX_4") (pintype "unspecified"))
    )
    (net (code "239") (name "Z2RX") (class "Default")
      (node (ref "BRAIN") (pin "4") (pinfunction "PE5/DCMI_D6/FMC_A21/LTDC_G0/SAI1_SCK_A/SPI4_MISO/SYS_TRACED2/TIM9_CH1_4") (pintype "bidirectional"))
      (node (ref "J44") (pin "2") (pinfunction "2_2") (pintype "unspecified"))
      (node (ref "U5") (pin "5") (pinfunction "RX_5") (pintype "unspecified"))
    )
    (net (code "240") (name "Z2TX") (class "Default")
      (node (ref "BRAIN") (pin "5") (pinfunction "PE6/DCMI_D7/FMC_A22/LTDC_G1/SAI1_SD_A/SAI2_MCLK_B/SPI4_MOSI/SYS_TRACED3/TIM1_BKIN2/TIM9_CH2_5") (pintype "bidirectional"))
      (node (ref "J43") (pin "6") (pinfunction "6_6") (pintype "input"))
      (node (ref "U5") (pin "4") (pinfunction "TX_4") (pintype "unspecified"))
    )
    (net (code "241") (name "ZDIR1") (class "Default")
      (node (ref "BRAIN") (pin "10") (pinfunction "PF0/FMC_A0/I2C2_SDA_10") (pintype "bidirectional"))
      (node (ref "U4") (pin "8") (pinfunction "DIR_8") (pintype "unspecified"))
    )
    (net (code "242") (name "ZDIR2") (class "Default")
      (node (ref "BRAIN") (pin "3") (pinfunction "PE4/DCMI_D4/FMC_A20/LTDC_B0/SAI1_FS_A/SPI4_NSS/SYS_TRACED1_3") (pintype "bidirectional"))
      (node (ref "U5") (pin "8") (pinfunction "DIR_8") (pintype "unspecified"))
    )
    (net (code "243") (name "ZEN1") (class "Default")
      (node (ref "BRAIN") (pin "13") (pinfunction "PF3/ADC3_IN9/FMC_A3_13") (pintype "bidirectional"))
      (node (ref "R25") (pin "2") (pinfunction "2_2") (pintype "unspecified"))
      (node (ref "U4") (pin "1") (pinfunction "EN_1") (pintype "unspecified"))
    )
    (net (code "244") (name "ZEN2") (class "Default")
      (node (ref "BRAIN") (pin "7") (pinfunction "RTC_OUT_ALARM/RTC_OUT_CALIB/RTC_TAMP1/RTC_TS/SYS_WKUP2/PC13_7") (pintype "bidirectional"))
      (node (ref "R26") (pin "2") (pinfunction "2_2") (pintype "unspecified"))
      (node (ref "U5") (pin "1") (pinfunction "EN_1") (pintype "unspecified"))
    )
    (net (code "245") (name "ZMAX") (class "Default")
      (node (ref "BRAIN") (pin "55") (pinfunction "PF15/FMC_A9/I2C4_SDA_55") (pintype "bidirectional"))
      (node (ref "Z1MAX") (pin "3") (pinfunction "3_3") (pintype "input"))
    )
    (net (code "246") (name "ZMAX2") (class "Default")
      (node (ref "BRAIN") (pin "57") (pinfunction "PG1/FMC_A11_57") (pintype "bidirectional"))
      (node (ref "Z2MAX") (pin "3") (pinfunction "3_3") (pintype "input"))
    )
    (net (code "247") (name "ZMIN") (class "Default")
      (node (ref "BRAIN") (pin "54") (pinfunction "PF14/FMC_A8/I2C4_SCL_54") (pintype "bidirectional"))
      (node (ref "Z1MIN") (pin "3") (pinfunction "3_3") (pintype "input"))
    )
    (net (code "248") (name "ZMIN2") (class "Default")
      (node (ref "BRAIN") (pin "56") (pinfunction "PG0/FMC_A10_56") (pintype "bidirectional"))
      (node (ref "Z2MIN") (pin "3") (pinfunction "3_3") (pintype "input"))
    )
    (net (code "249") (name "ZSTEP1") (class "Default")
      (node (ref "BRAIN") (pin "9") (pinfunction "RCC_OSC32_OUT/PC15_9") (pintype "bidirectional"))
      (node (ref "U4") (pin "7") (pinfunction "STEP_7") (pintype "unspecified"))
    )
    (net (code "250") (name "ZSTEP2") (class "Default")
      (node (ref "BRAIN") (pin "2") (pinfunction "PE3/FMC_A19/SAI1_SD_B/SYS_TRACED0_2") (pintype "bidirectional"))
      (node (ref "U5") (pin "7") (pinfunction "STEP_7") (pintype "unspecified"))
    )
    (net (code "251") (name "unconnected-(SDCARD-NC-Pad1)") (class "Default")
      (node (ref "SDCARD") (pin "1") (pinfunction "NC_1") (pintype "bidirectional+no_connect"))
    )
    (net (code "252") (name "unconnected-(SDCARD-NC-Pad8)") (class "Default")
      (node (ref "SDCARD") (pin "8") (pinfunction "NC_8") (pintype "input+no_connect"))
    )
    (net (code "253") (name "unconnected-(U2-INDEX-Pad17)") (class "Default")
      (node (ref "U2") (pin "17") (pinfunction "INDEX_17") (pintype "unspecified"))
    )
    (net (code "254") (name "unconnected-(U3-GND-Pad9)") (class "Default")
      (node (ref "U3") (pin "9") (pinfunction "GND_9") (pintype "unspecified"))
    )
    (net (code "255") (name "unconnected-(U3-INDEX-Pad17)") (class "Default")
      (node (ref "U3") (pin "17") (pinfunction "INDEX_17") (pintype "unspecified"))
    )
    (net (code "256") (name "unconnected-(U4-INDEX-Pad17)") (class "Default")
      (node (ref "U4") (pin "17") (pinfunction "INDEX_17") (pintype "unspecified"))
    )
    (net (code "257") (name "unconnected-(U5-INDEX-Pad17)") (class "Default")
      (node (ref "U5") (pin "17") (pinfunction "INDEX_17") (pintype "unspecified"))
    )
    (net (code "258") (name "unconnected-(U6-TAB-Pad4)") (class "Default")
      (node (ref "U6") (pin "4") (pinfunction "TAB_4") (pintype "unspecified"))
    )
    (net (code "259") (name "unconnected-(U7-INDEX-Pad17)") (class "Default")
      (node (ref "U7") (pin "17") (pinfunction "INDEX_17") (pintype "unspecified"))
    )
    (net (code "260") (name "unconnected-(U8-INDEX-Pad17)") (class "Default")
      (node (ref "U8") (pin "17") (pinfunction "INDEX_17") (pintype "unspecified"))
    )
    (net (code "261") (name "unconnected-(U9-INDEX-Pad17)") (class "Default")
      (node (ref "U9") (pin "17") (pinfunction "INDEX_17") (pintype "unspecified"))
    )
    (net (code "262") (name "unconnected-(U10-INDEX-Pad17)") (class "Default")
      (node (ref "U10") (pin "17") (pinfunction "INDEX_17") (pintype "unspecified"))
    )
    (net (code "263") (name "unconnected-(U18-IN5-Pad5)") (class "Default")
      (node (ref "U18") (pin "5") (pinfunction "IN5_5") (pintype "unspecified"))
    )
    (net (code "264") (name "unconnected-(U18-IN6-Pad6)") (class "Default")
      (node (ref "U18") (pin "6") (pinfunction "IN6_6") (pintype "unspecified"))
    )
    (net (code "265") (name "unconnected-(U18-IN7-Pad7)") (class "Default")
      (node (ref "U18") (pin "7") (pinfunction "IN7_7") (pintype "unspecified"))
    )
    (net (code "266") (name "unconnected-(U18-OUT5-Pad12)") (class "Default")
      (node (ref "U18") (pin "12") (pinfunction "OUT5_12") (pintype "unspecified"))
    )
    (net (code "267") (name "unconnected-(U18-OUT6-Pad11)") (class "Default")
      (node (ref "U18") (pin "11") (pinfunction "OUT6_11") (pintype "unspecified"))
    )
    (net (code "268") (name "unconnected-(U18-OUT7-Pad10)") (class "Default")
      (node (ref "U18") (pin "10") (pinfunction "OUT7_10") (pintype "unspecified"))
    )
    (net (code "269") (name "unconnected-(U19-IN5-Pad5)") (class "Default")
      (node (ref "U19") (pin "5") (pinfunction "IN5_5") (pintype "unspecified"))
    )
    (net (code "270") (name "unconnected-(U19-IN6-Pad6)") (class "Default")
      (node (ref "U19") (pin "6") (pinfunction "IN6_6") (pintype "unspecified"))
    )
    (net (code "271") (name "unconnected-(U19-IN7-Pad7)") (class "Default")
      (node (ref "U19") (pin "7") (pinfunction "IN7_7") (pintype "unspecified"))
    )
    (net (code "272") (name "unconnected-(U19-OUT5-Pad12)") (class "Default")
      (node (ref "U19") (pin "12") (pinfunction "OUT5_12") (pintype "unspecified"))
    )
    (net (code "273") (name "unconnected-(U19-OUT6-Pad11)") (class "Default")
      (node (ref "U19") (pin "11") (pinfunction "OUT6_11") (pintype "unspecified"))
    )
    (net (code "274") (name "unconnected-(U19-OUT7-Pad10)") (class "Default")
      (node (ref "U19") (pin "10") (pinfunction "OUT7_10") (pintype "unspecified"))
    )
    (net (code "275") (name "unconnected-(USB_OTG-Pad1)") (class "Default")
      (node (ref "USB_OTG") (pin "1") (pinfunction "1_1") (pintype "bidirectional"))
    )
    (net (code "276") (name "unconnected-(USB_SER-GP0{slash}SSPND-Pad16)") (class "Default")
      (node (ref "USB_SER") (pin "16") (pinfunction "GP0/SSPND_16") (pintype "unspecified"))
    )
    (net (code "277") (name "unconnected-(USB_SER-GP1{slash}USBCFG-Pad15)") (class "Default")
      (node (ref "USB_SER") (pin "15") (pinfunction "GP1/USBCFG_15") (pintype "unspecified"))
    )
    (net (code "278") (name "unconnected-(USB_SER-GP2-Pad14)") (class "Default")
      (node (ref "USB_SER") (pin "14") (pinfunction "GP2_14") (pintype "unspecified"))
    )
    (net (code "279") (name "unconnected-(USB_SER-GP3-Pad9)") (class "Default")
      (node (ref "USB_SER") (pin "9") (pinfunction "GP3_9") (pintype "unspecified"))
    )
    (net (code "280") (name "unconnected-(USB_SER-GP4-Pad8)") (class "Default")
      (node (ref "USB_SER") (pin "8") (pinfunction "GP4_8") (pintype "unspecified"))
    )
    (net (code "281") (name "unconnected-(USB_SER-GP5-Pad7)") (class "Default")
      (node (ref "USB_SER") (pin "7") (pinfunction "GP5_7") (pintype "unspecified"))
    )
  )
)
